# range_cape.net
KiCad netlist of a schematic drawn in EAGLE
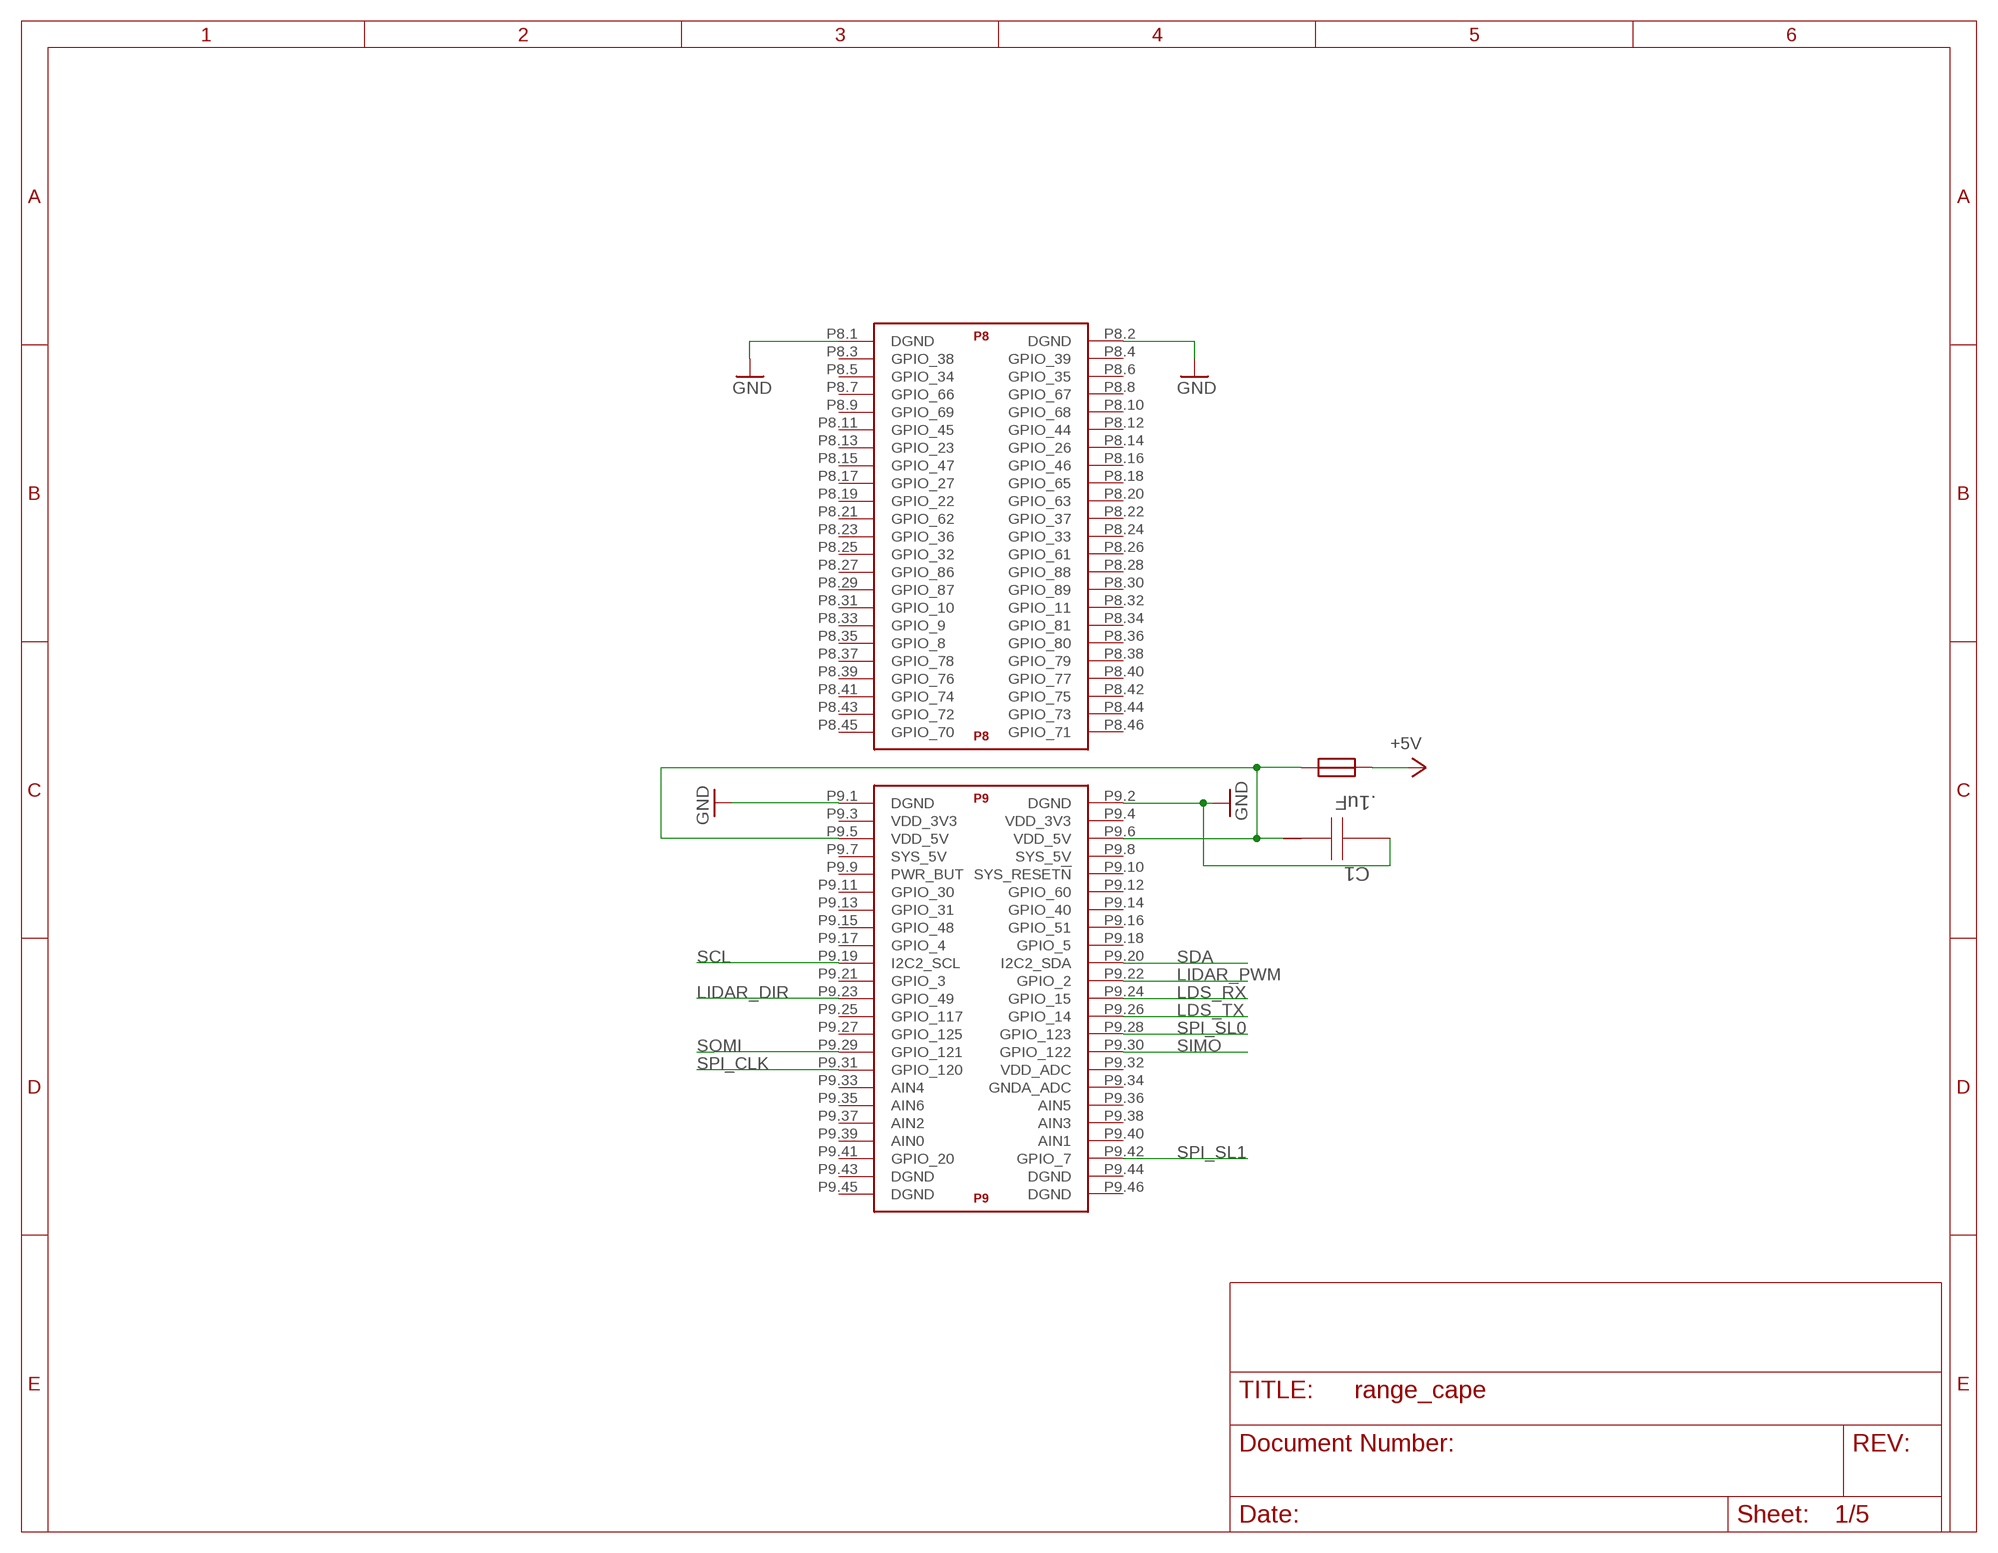
[diagram p0: schematic, sheet 1]
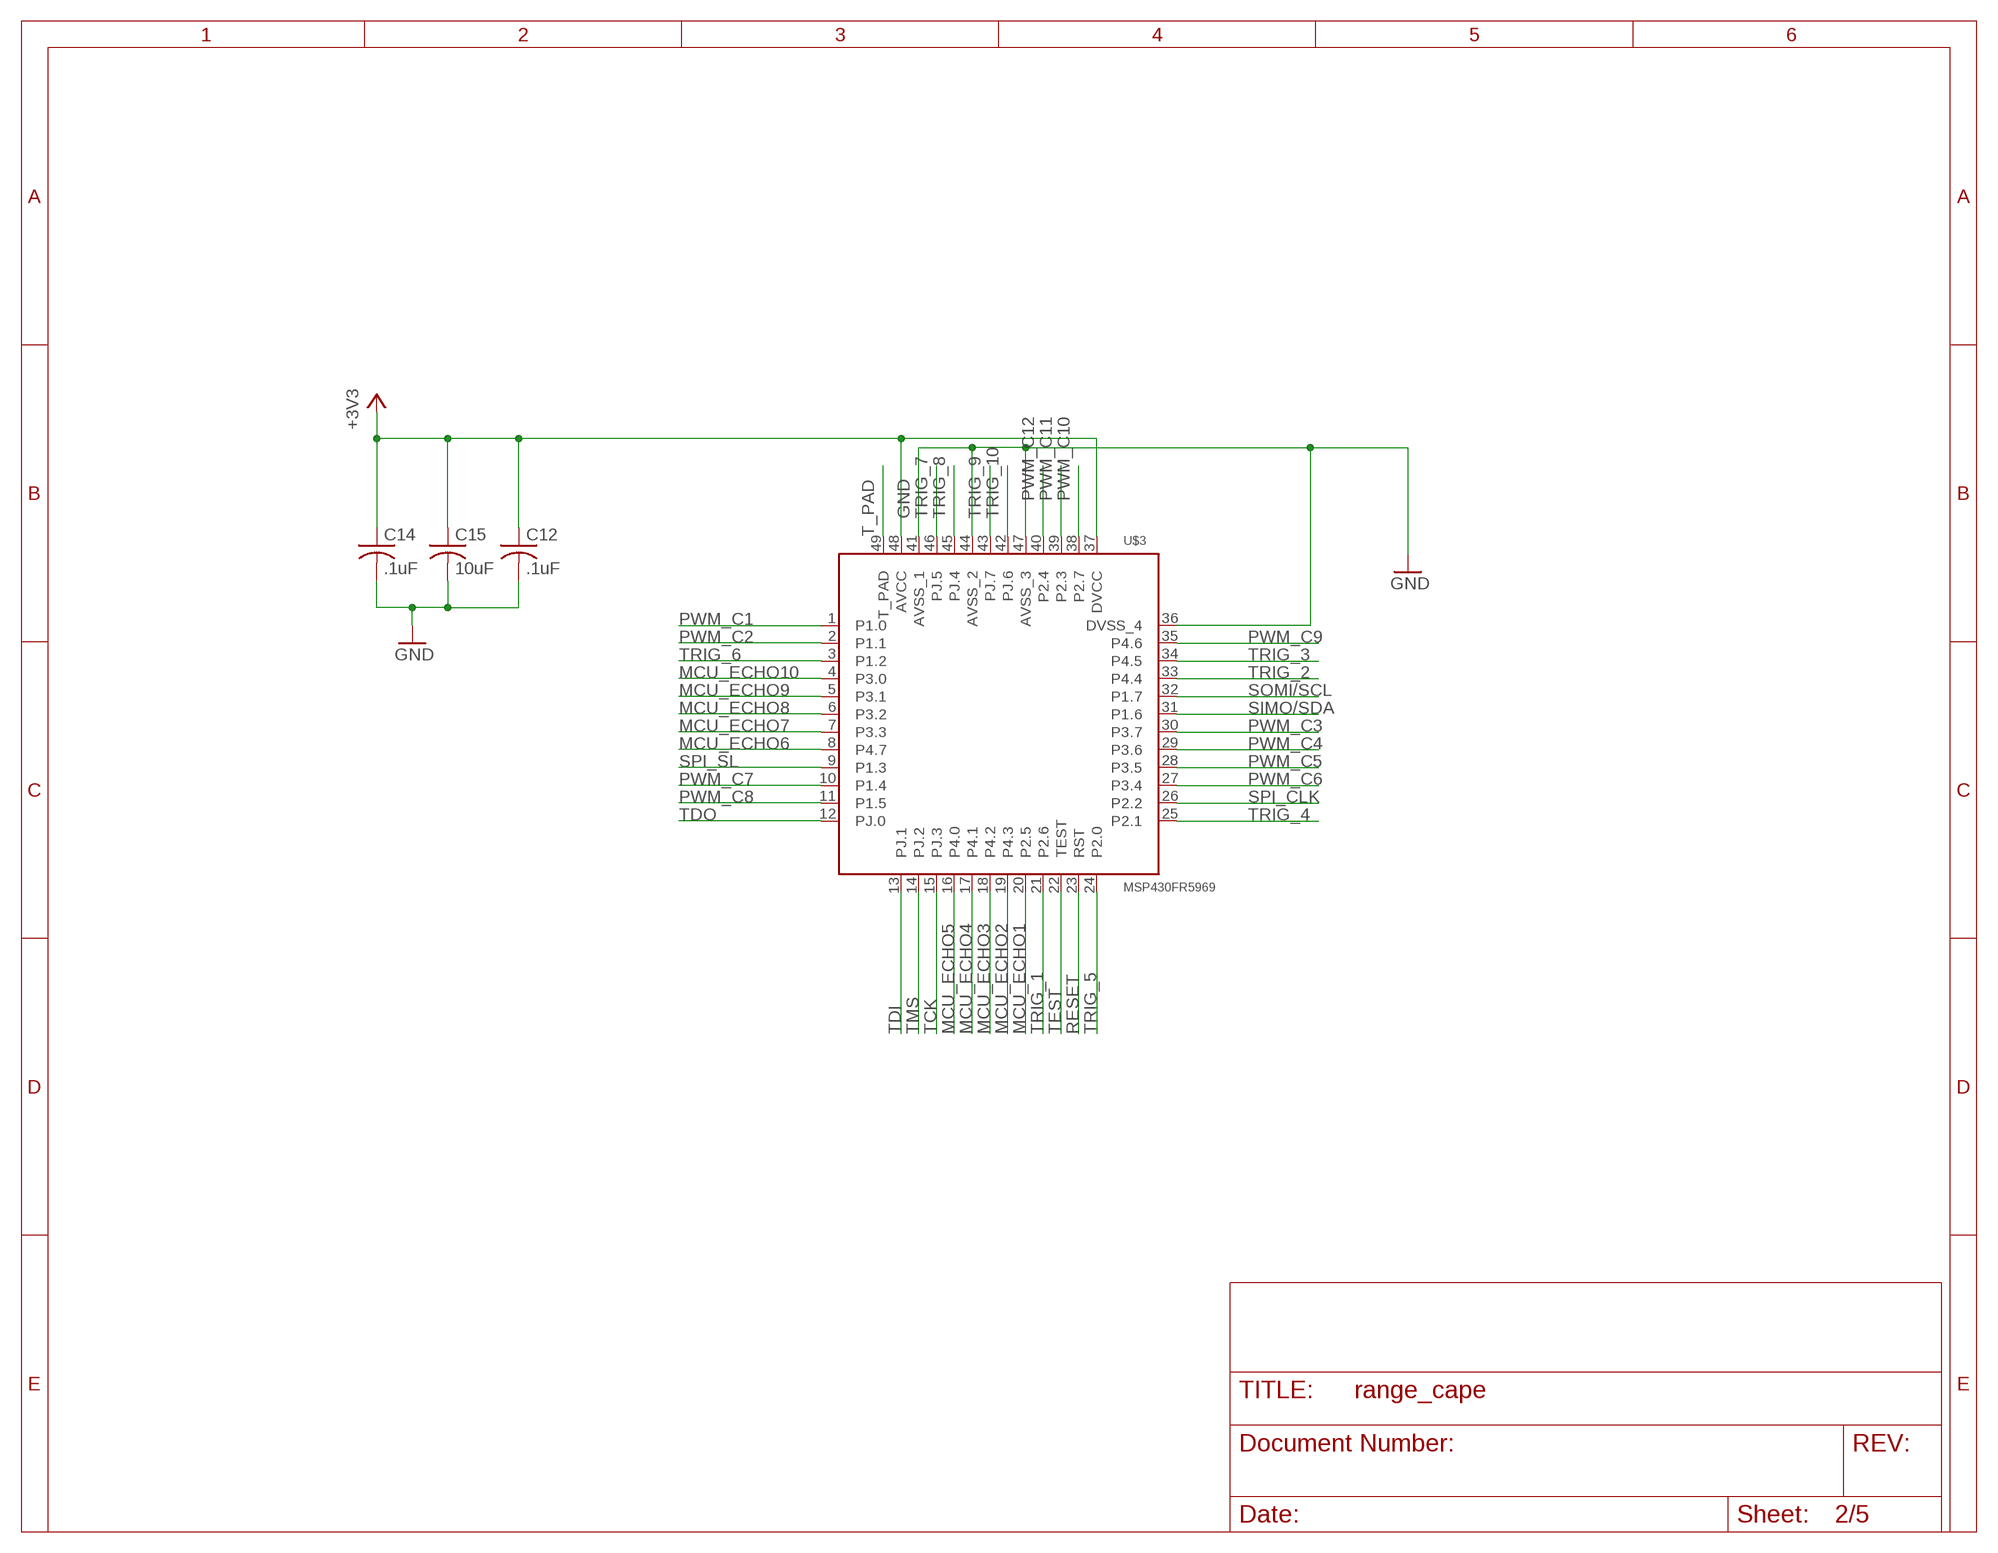
[diagram p1: schematic, sheet 2]
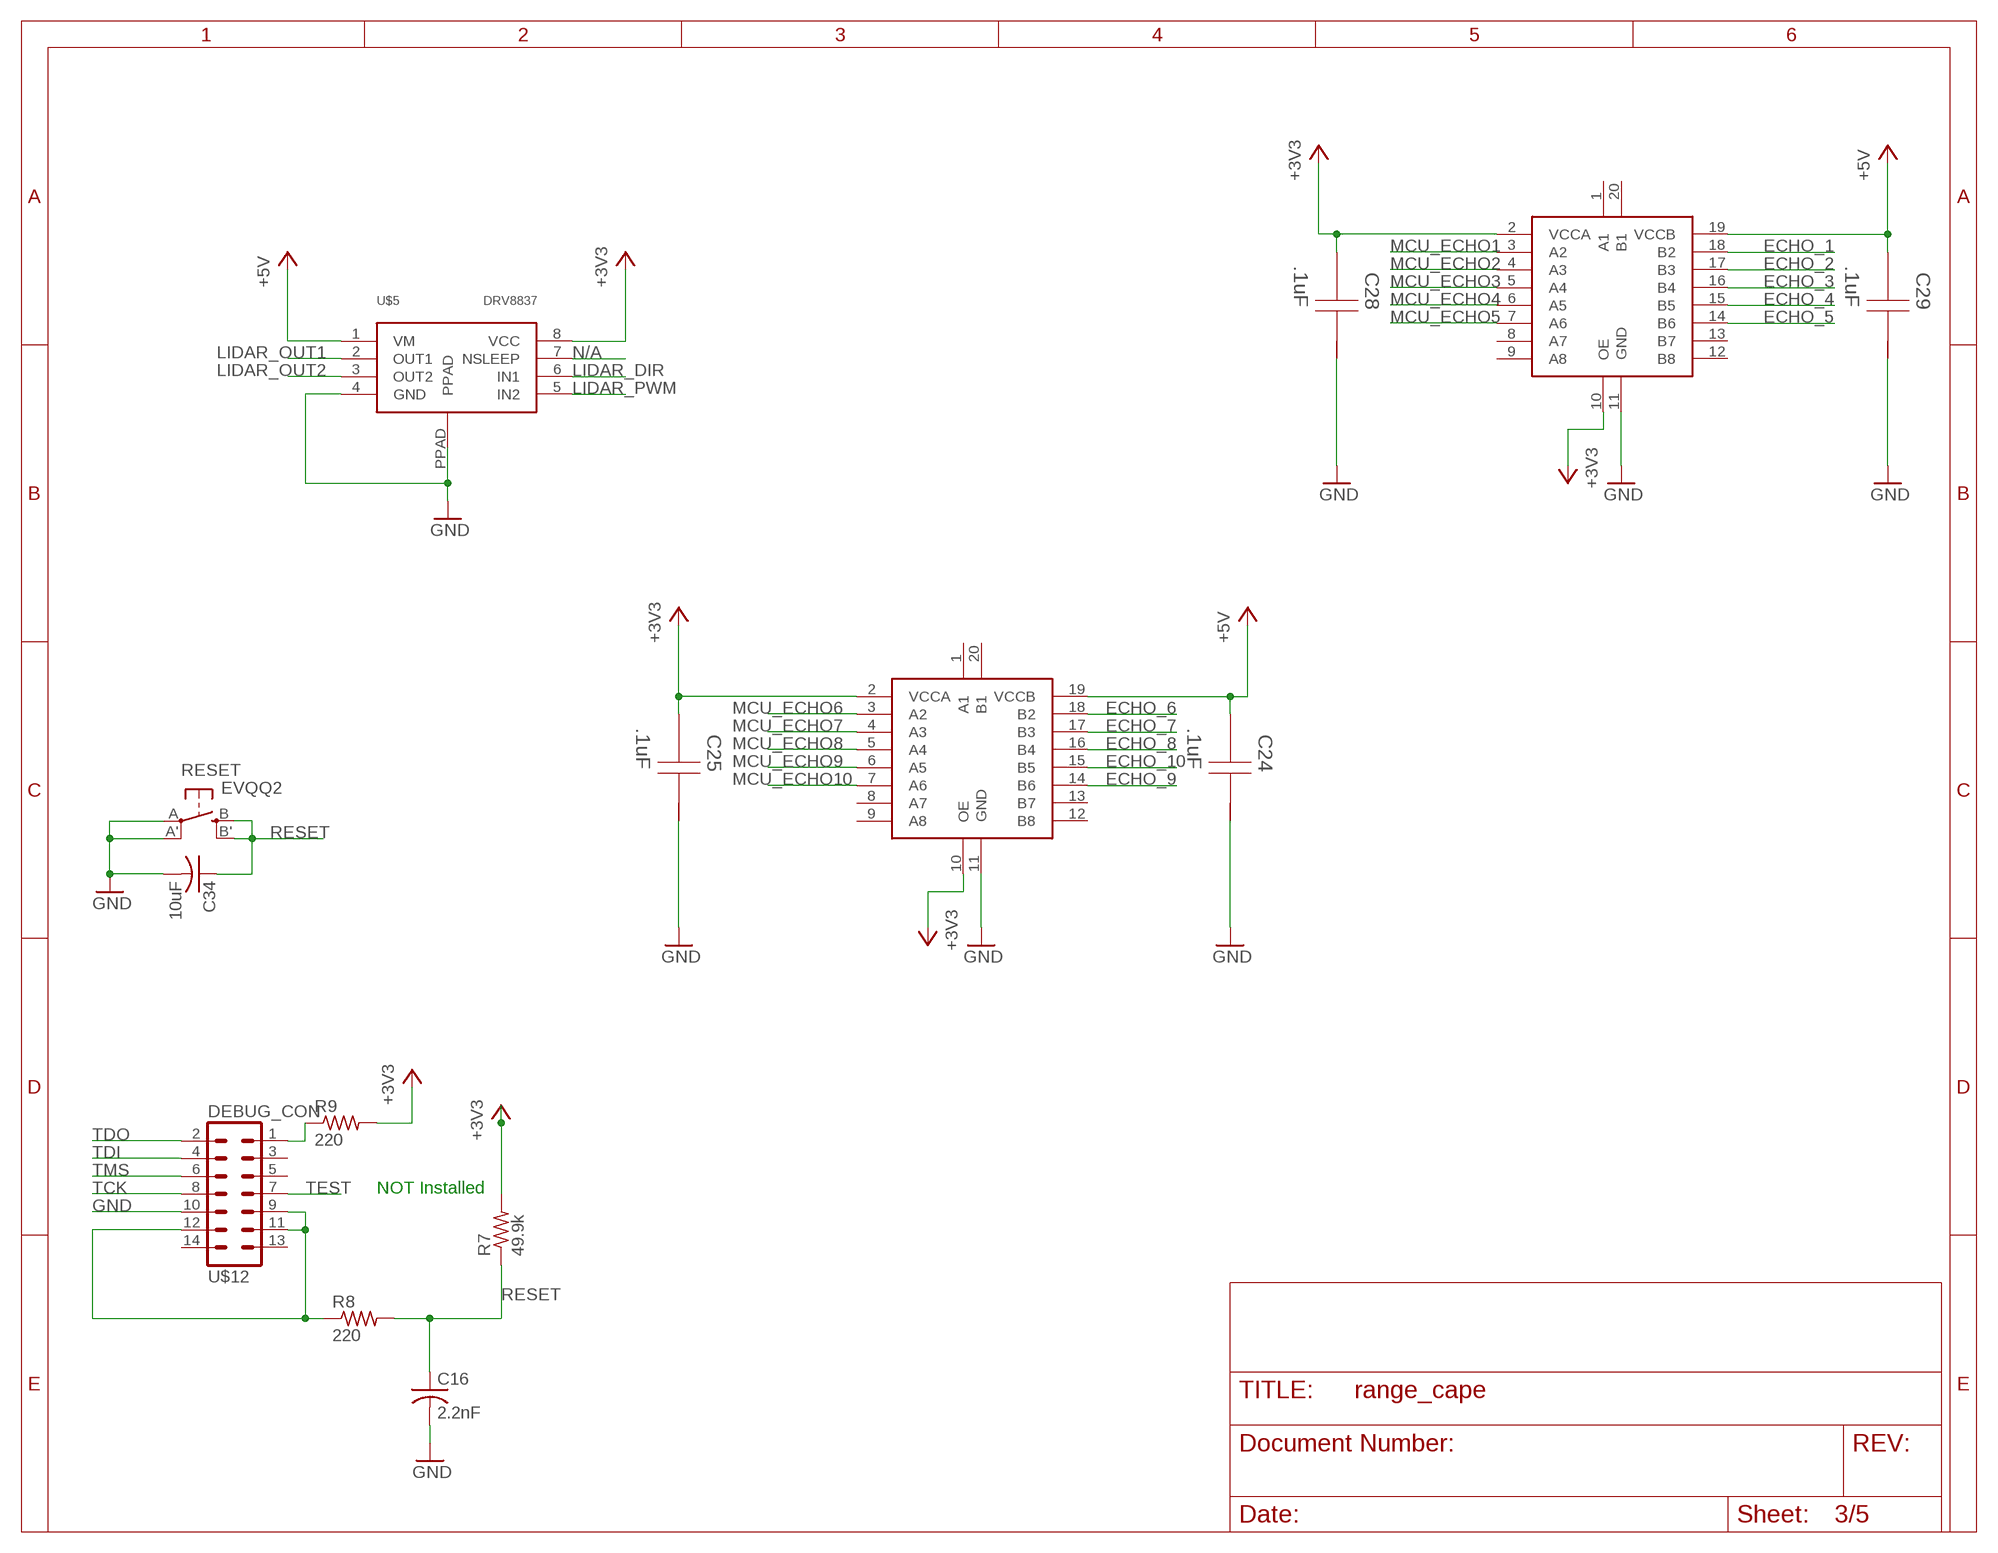
[diagram p2: schematic, sheet 3]
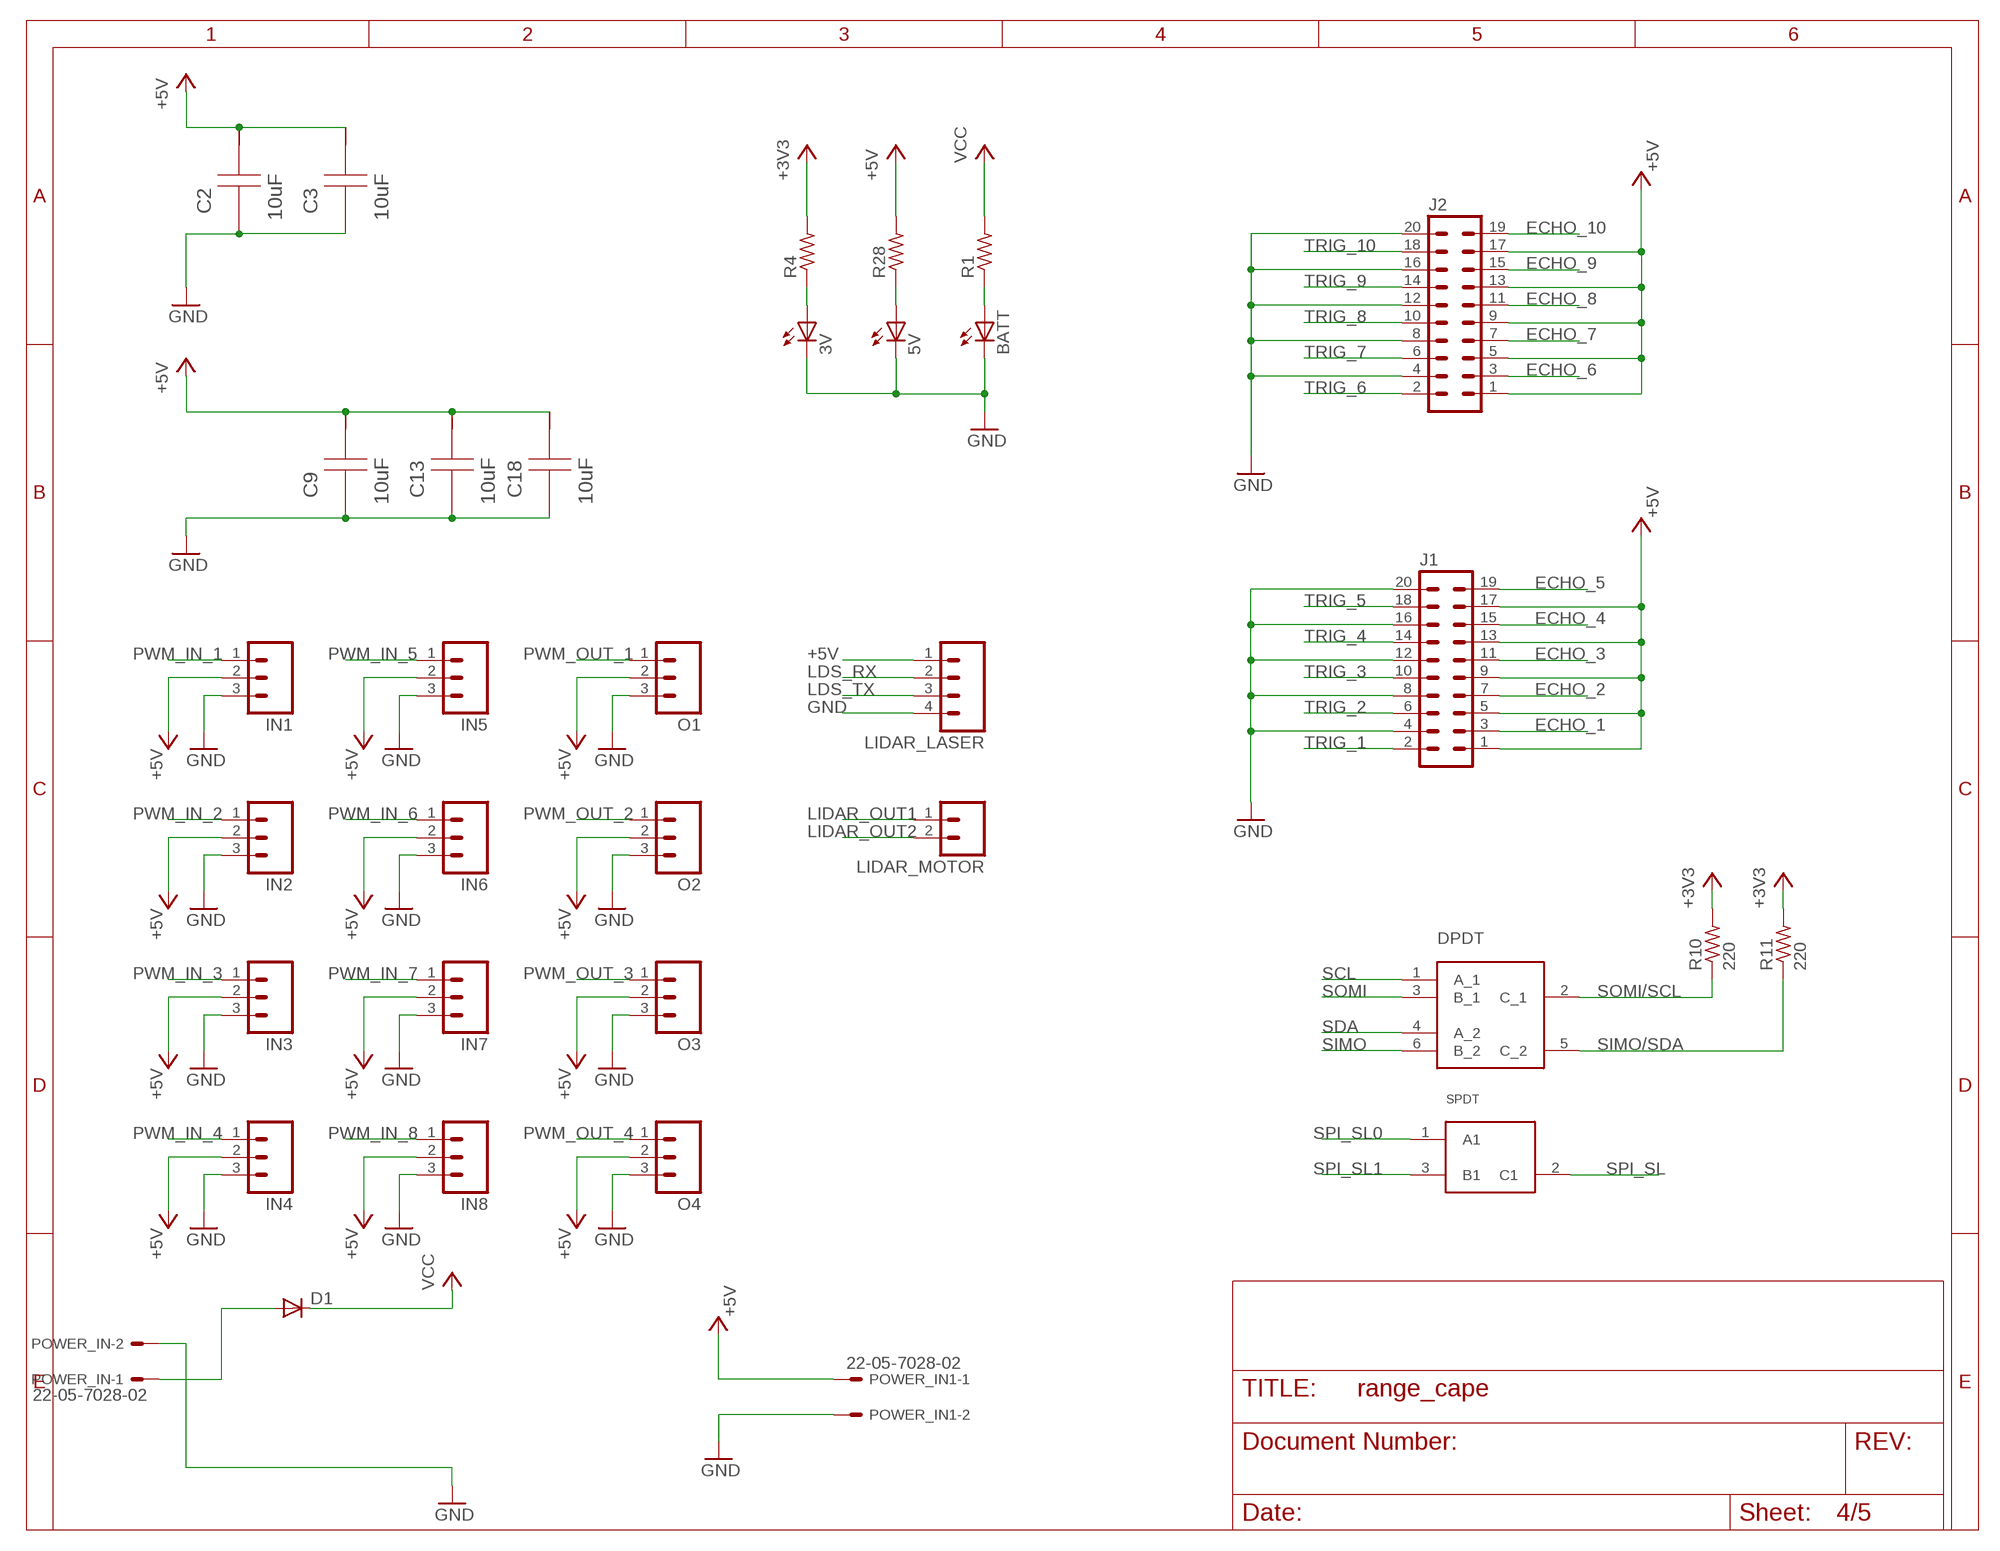
[diagram p3: schematic, sheet 4]
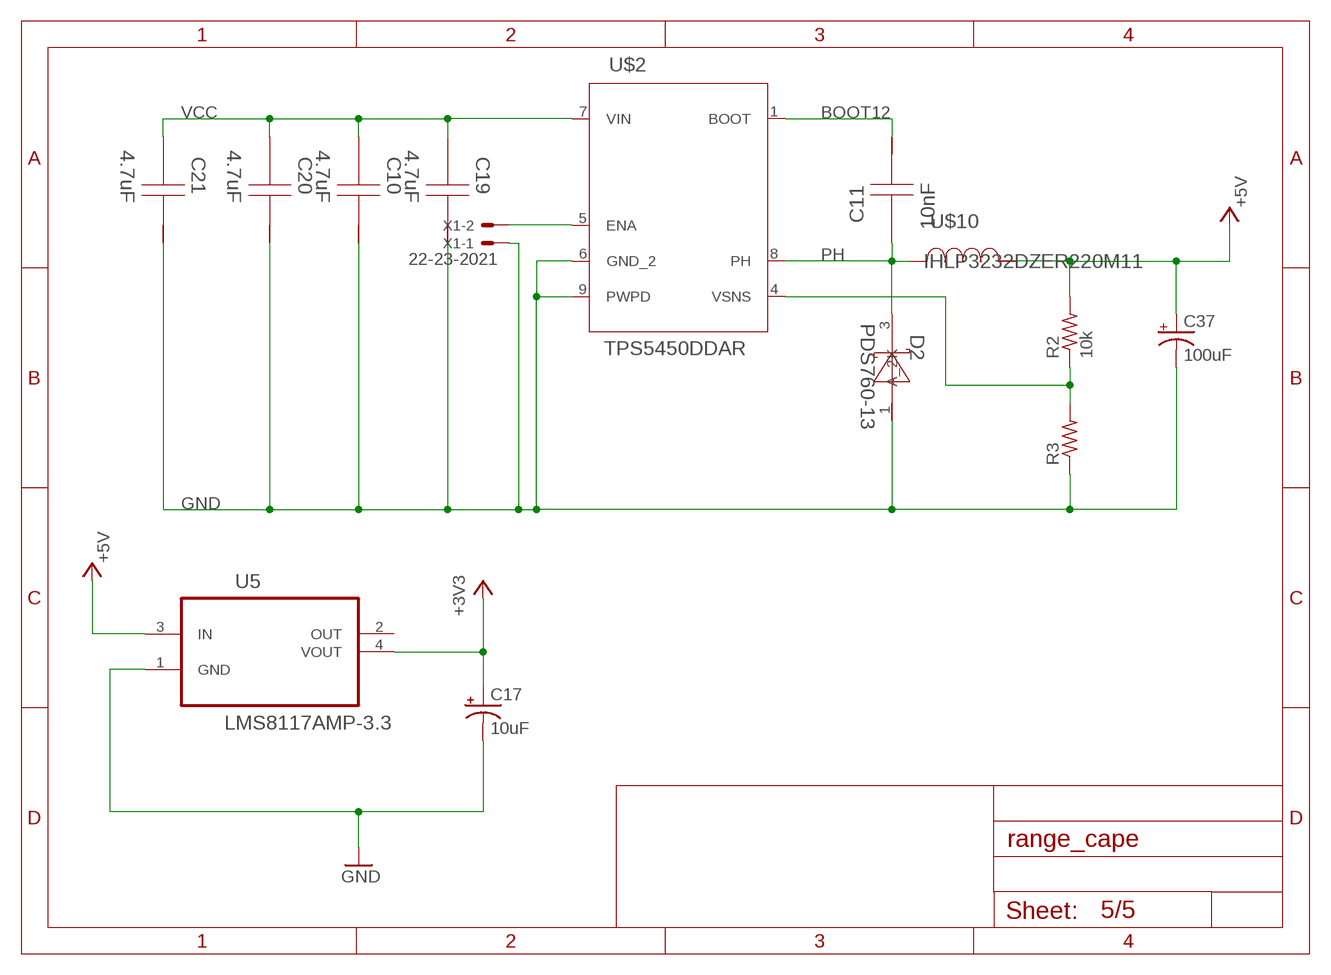
[diagram p4: schematic, sheet 5]

(export (version "E")
  (design (tool "Eeschema 10.0.6"))
  (components
    (comp (ref "C16")
      (value "2.2nF")
      (footprint "eagle-import:C0603")
      (libsource (lib "eagle-import") (part "C-USC0603"))
    )
    (comp (ref "C24")
      (value ".1uF")
      (footprint "eagle-import:1206")
      (fields (field (name "MANUFACTURER_PART_NUMBER") "C3216X5R1A106K"))
      (libsource (lib "eagle-import") (part "C3216X5R1A106K"))
    )
    (comp (ref "C25")
      (value ".1uF")
      (footprint "eagle-import:1206")
      (fields (field (name "MANUFACTURER_PART_NUMBER") "C3216X5R1A106K"))
      (libsource (lib "eagle-import") (part "C3216X5R1A106K"))
    )
    (comp (ref "C28")
      (value ".1uF")
      (footprint "eagle-import:1206")
      (fields (field (name "MANUFACTURER_PART_NUMBER") "C3216X5R1A106K"))
      (libsource (lib "eagle-import") (part "C3216X5R1A106K"))
    )
    (comp (ref "C29")
      (value ".1uF")
      (footprint "eagle-import:1206")
      (fields (field (name "MANUFACTURER_PART_NUMBER") "C3216X5R1A106K"))
      (libsource (lib "eagle-import") (part "C3216X5R1A106K"))
    )
    (comp (ref "C34")
      (value "10uF")
      (footprint "eagle-import:C1206")
      (libsource (lib "eagle-import") (part "C-USC1206"))
    )
    (comp (ref "R7")
      (value "49.9k")
      (footprint "eagle-import:R0603")
      (libsource (lib "eagle-import") (part "rcl_R-US_R0603"))
    )
    (comp (ref "R8")
      (value "220")
      (footprint "eagle-import:R0603")
      (libsource (lib "eagle-import") (part "rcl_R-US_R0603"))
    )
    (comp (ref "R9")
      (value "220")
      (footprint "eagle-import:R0603")
      (libsource (lib "eagle-import") (part "rcl_R-US_R0603"))
    )
    (comp (ref "RESET")
      (value "EVQQ2")
      (footprint "eagle-import:EVQ-Q2")
      (libsource (lib "eagle-import") (part "EVQQ2"))
    )
    (comp (ref "U$5")
      (value "DRV8837")
      (footprint "eagle-import:WSON-8")
      (libsource (lib "eagle-import") (part "DRV8837"))
    )
    (comp (ref "U$6")
      (value "TXB0108")
      (footprint "eagle-import:TSSOP-20")
      (libsource (lib "eagle-import") (part "TXB0108"))
    )
    (comp (ref "U$8")
      (value "TXB0108")
      (footprint "eagle-import:TSSOP-20")
      (libsource (lib "eagle-import") (part "TXB0108"))
    )
    (comp (ref "U$12")
      (value "DEBUG_CON")
      (footprint "eagle-import:DEBUG_SM")
      (libsource (lib "eagle-import") (part "DEBUG_CON"))
    )
    (comp (ref "C10")
      (value "4.7uF")
      (footprint "eagle-import:1206")
      (fields (field (name "MANUFACTURER_PART_NUMBER") "GRM31CR71H475KA12L"))
      (libsource (lib "eagle-import") (part "GRM31CR71H475KA12L"))
    )
    (comp (ref "C11")
      (value "10nF")
      (footprint "eagle-import:0805")
      (fields (field (name "MANUFACTURER_PART_NUMBER") "C0805C103K5RACTU"))
      (libsource (lib "eagle-import") (part "C0805C103K5RACTU"))
    )
    (comp (ref "C17")
      (value "10uF")
      (footprint "eagle-import:EIA3216")
      (libsource (lib "eagle-import") (part "10UF-16V-10%(TANT)"))
    )
    (comp (ref "C19")
      (value "4.7uF")
      (footprint "eagle-import:1206")
      (fields (field (name "MANUFACTURER_PART_NUMBER") "GRM31CR71H475KA12L"))
      (libsource (lib "eagle-import") (part "GRM31CR71H475KA12L"))
    )
    (comp (ref "C20")
      (value "4.7uF")
      (footprint "eagle-import:1206")
      (fields (field (name "MANUFACTURER_PART_NUMBER") "GRM31CR71H475KA12L"))
      (libsource (lib "eagle-import") (part "GRM31CR71H475KA12L"))
    )
    (comp (ref "C21")
      (value "4.7uF")
      (footprint "eagle-import:1206")
      (fields (field (name "MANUFACTURER_PART_NUMBER") "GRM31CR71H475KA12L"))
      (libsource (lib "eagle-import") (part "GRM31CR71H475KA12L"))
    )
    (comp (ref "C37")
      (value "100uF")
      (footprint "eagle-import:EIA7343")
      (libsource (lib "eagle-import") (part "100UF-10V-10%(TANT)"))
    )
    (comp (ref "D2")
      (value "PDS760-13")
      (footprint "eagle-import:POWERDI5")
      (libsource (lib "eagle-import") (part "PDS760-13"))
    )
    (comp (ref "R2")
      (value "10k")
      (footprint "eagle-import:M0805")
      (libsource (lib "eagle-import") (part "R-US_M0805"))
    )
    (comp (ref "R3")
      (value "R-US_M0805")
      (footprint "eagle-import:M0805")
      (libsource (lib "eagle-import") (part "R-US_M0805"))
    )
    (comp (ref "U$2")
      (value "TPS5450DDAR")
      (footprint "eagle-import:R-PDSO-G8")
      (fields (field (name "MANUFACTURER_PART_NUMBER") "TPS5450DDA"))
      (libsource (lib "eagle-import") (part "TPS5450DDAR"))
    )
    (comp (ref "U$10")
      (value "IHLP3232DZER220M11")
      (footprint "eagle-import:IHLP-3232DZ")
      (fields (field (name "MANUFACTURER") "Vishay"))
      (libsource (lib "eagle-import") (part "IHLP3232DZER220M11"))
    )
    (comp (ref "U5")
      (value "LMS8117AMP-3.3")
      (footprint "eagle-import:SOT230P696X180-4N")
      (libsource (lib "eagle-import") (part "LMS8117AMP-3.3"))
    )
    (comp (ref "X1")
      (value "22-23-2021")
      (footprint "eagle-import:22-23-2021")
      (fields (field (name "MF") "MOLEX"))
      (libsource (lib "eagle-import") (part "22-23-2021"))
    )
    (comp (ref "3V")
      (value "LED_ESML0603")
      (footprint "eagle-import:LED_SML0603")
      (libsource (lib "eagle-import") (part "LED_ESML0603"))
    )
    (comp (ref "5V")
      (value "LED_ESML0603")
      (footprint "eagle-import:LED_SML0603")
      (libsource (lib "eagle-import") (part "LED_ESML0603"))
    )
    (comp (ref "BATT")
      (value "LED_ESML0603")
      (footprint "eagle-import:LED_SML0603")
      (libsource (lib "eagle-import") (part "LED_ESML0603"))
    )
    (comp (ref "C2")
      (value "10uF")
      (footprint "eagle-import:1206")
      (fields (field (name "MANUFACTURER_PART_NUMBER") "C3216X5R1A106K"))
      (libsource (lib "eagle-import") (part "C3216X5R1A106K"))
    )
    (comp (ref "C3")
      (value "10uF")
      (footprint "eagle-import:1206")
      (fields (field (name "MANUFACTURER_PART_NUMBER") "C3216X5R1A106K"))
      (libsource (lib "eagle-import") (part "C3216X5R1A106K"))
    )
    (comp (ref "C9")
      (value "10uF")
      (footprint "eagle-import:1206")
      (fields (field (name "MANUFACTURER_PART_NUMBER") "C3216X5R1A106K"))
      (libsource (lib "eagle-import") (part "C3216X5R1A106K"))
    )
    (comp (ref "C13")
      (value "10uF")
      (footprint "eagle-import:1206")
      (fields (field (name "MANUFACTURER_PART_NUMBER") "C3216X5R1A106K"))
      (libsource (lib "eagle-import") (part "C3216X5R1A106K"))
    )
    (comp (ref "C18")
      (value "10uF")
      (footprint "eagle-import:1206")
      (fields (field (name "MANUFACTURER_PART_NUMBER") "C3216X5R1A106K"))
      (libsource (lib "eagle-import") (part "C3216X5R1A106K"))
    )
    (comp (ref "D1")
      (value "DIODE-DO-214AC")
      (footprint "eagle-import:DO-214AC")
      (libsource (lib "eagle-import") (part "DIODE-DO-214AC"))
    )
    (comp (ref "IN1")
      (value "M03LOCK")
      (footprint "eagle-import:1X03_LOCK")
      (libsource (lib "eagle-import") (part "M03LOCK"))
    )
    (comp (ref "IN2")
      (value "M03LOCK")
      (footprint "eagle-import:1X03_LOCK")
      (libsource (lib "eagle-import") (part "M03LOCK"))
    )
    (comp (ref "IN3")
      (value "M03LOCK")
      (footprint "eagle-import:1X03_LOCK")
      (libsource (lib "eagle-import") (part "M03LOCK"))
    )
    (comp (ref "IN4")
      (value "M03LOCK")
      (footprint "eagle-import:1X03_LOCK")
      (libsource (lib "eagle-import") (part "M03LOCK"))
    )
    (comp (ref "IN5")
      (value "M03LOCK")
      (footprint "eagle-import:1X03_LOCK")
      (libsource (lib "eagle-import") (part "M03LOCK"))
    )
    (comp (ref "IN6")
      (value "M03LOCK")
      (footprint "eagle-import:1X03_LOCK")
      (libsource (lib "eagle-import") (part "M03LOCK"))
    )
    (comp (ref "IN7")
      (value "M03LOCK")
      (footprint "eagle-import:1X03_LOCK")
      (libsource (lib "eagle-import") (part "M03LOCK"))
    )
    (comp (ref "IN8")
      (value "M03LOCK")
      (footprint "eagle-import:1X03_LOCK")
      (libsource (lib "eagle-import") (part "M03LOCK"))
    )
    (comp (ref "J1")
      (value "MA10-2")
      (footprint "eagle-import:MA10-2")
      (libsource (lib "eagle-import") (part "MA10-2"))
    )
    (comp (ref "J2")
      (value "MA10-2")
      (footprint "eagle-import:MA10-2")
      (libsource (lib "eagle-import") (part "MA10-2"))
    )
    (comp (ref "LIDAR_LASER")
      (value "M04JST-PTH-VERT")
      (footprint "eagle-import:JST-4-PTH-VERT")
      (libsource (lib "eagle-import") (part "M04JST-PTH-VERT"))
    )
    (comp (ref "LIDAR_MOTOR")
      (value "M02JST-PTH-VERT")
      (footprint "eagle-import:JST-2-PTH-VERT")
      (libsource (lib "eagle-import") (part "M02JST-PTH-VERT"))
    )
    (comp (ref "O1")
      (value "M03LOCK")
      (footprint "eagle-import:1X03_LOCK")
      (libsource (lib "eagle-import") (part "M03LOCK"))
    )
    (comp (ref "O2")
      (value "M03LOCK")
      (footprint "eagle-import:1X03_LOCK")
      (libsource (lib "eagle-import") (part "M03LOCK"))
    )
    (comp (ref "O3")
      (value "M03LOCK")
      (footprint "eagle-import:1X03_LOCK")
      (libsource (lib "eagle-import") (part "M03LOCK"))
    )
    (comp (ref "O4")
      (value "M03LOCK")
      (footprint "eagle-import:1X03_LOCK")
      (libsource (lib "eagle-import") (part "M03LOCK"))
    )
    (comp (ref "POWER_IN")
      (value "22-05-7028-02")
      (footprint "eagle-import:7395-02")
      (libsource (lib "eagle-import") (part "22-?-0205-7028"))
    )
    (comp (ref "POWER_IN1")
      (value "22-05-7028-02")
      (footprint "eagle-import:7395-02")
      (libsource (lib "eagle-import") (part "22-?-0205-7028"))
    )
    (comp (ref "R1")
      (value "R-US_R0603")
      (footprint "eagle-import:R0603")
      (libsource (lib "eagle-import") (part "rcl_R-US_R0603"))
    )
    (comp (ref "R4")
      (value "R-US_R0603")
      (footprint "eagle-import:R0603")
      (libsource (lib "eagle-import") (part "rcl_R-US_R0603"))
    )
    (comp (ref "R10")
      (value "220")
      (footprint "eagle-import:R0402")
      (libsource (lib "eagle-import") (part "rcl_R-US_R0402"))
    )
    (comp (ref "R11")
      (value "220")
      (footprint "eagle-import:R0402")
      (libsource (lib "eagle-import") (part "rcl_R-US_R0402"))
    )
    (comp (ref "R28")
      (value "R-US_R0603")
      (footprint "eagle-import:R0603")
      (libsource (lib "eagle-import") (part "rcl_R-US_R0603"))
    )
    (comp (ref "SPDT")
      (value "SPDT_SWITCH")
      (footprint "eagle-import:SPDT")
      (libsource (lib "eagle-import") (part "SPDT_SWITCH"))
    )
    (comp (ref "U$4")
      (value "DPDT_I2C_SPI")
      (footprint "eagle-import:DPDT")
      (libsource (lib "eagle-import") (part "DPDT_I2C_SPI"))
    )
    (comp (ref "C12")
      (value ".1uF")
      (footprint "eagle-import:C0805")
      (libsource (lib "eagle-import") (part "C-USC0805"))
    )
    (comp (ref "C14")
      (value ".1uF")
      (footprint "eagle-import:C0805")
      (libsource (lib "eagle-import") (part "C-USC0805"))
    )
    (comp (ref "C15")
      (value "10uF")
      (footprint "eagle-import:C0805")
      (libsource (lib "eagle-import") (part "C-USC0805"))
    )
    (comp (ref "U$3")
      (value "MSP430FR5969")
      (footprint "eagle-import:QFN50P700X700X100-49N")
      (libsource (lib "eagle-import") (part "MSP430FR5969"))
    )
    (comp (ref "C1")
      (value ".1uF")
      (footprint "eagle-import:1206")
      (fields (field (name "MANUFACTURER_PART_NUMBER") "C3216X5R1A106K"))
      (libsource (lib "eagle-import") (part "C3216X5R1A106K"))
    )
    (comp (ref "U$1")
      (value "BEAGLE_BONE_BLACK_CAPE")
      (footprint "eagle-import:BEAGLE_BONE_BLACK_CAPE")
      (libsource (lib "eagle-import") (part "BEAGLE_BONE_BLACK_CAPE"))
    )
    (comp (ref "U$11")
      (value "NANO_FUSE")
      (footprint "eagle-import:NANO_FUSE")
      (libsource (lib "eagle-import") (part "NANO_FUSE"))
    )
  )
  (nets
    (net (code "1") (name "+3V3") (class "Default")
      (node (ref "C12") (pin "1") (pinfunction "1_1") (pintype "passive"))
      (node (ref "C14") (pin "1") (pinfunction "1_1") (pintype "passive"))
      (node (ref "C15") (pin "1") (pinfunction "1_1") (pintype "passive"))
      (node (ref "C17") (pin "A") (pinfunction "+_A") (pintype "passive"))
      (node (ref "C25") (pin "2") (pinfunction "2_2") (pintype "passive"))
      (node (ref "C28") (pin "2") (pinfunction "2_2") (pintype "passive"))
      (node (ref "R10") (pin "2") (pinfunction "2_2") (pintype "passive"))
      (node (ref "R11") (pin "2") (pinfunction "2_2") (pintype "passive"))
      (node (ref "R4") (pin "2") (pinfunction "2_2") (pintype "passive"))
      (node (ref "R7") (pin "2") (pinfunction "2_2") (pintype "passive"))
      (node (ref "R9") (pin "2") (pinfunction "2_2") (pintype "passive"))
      (node (ref "U$3") (pin "37") (pinfunction "DVCC_37") (pintype "power_in"))
      (node (ref "U$3") (pin "48") (pinfunction "AVCC_48") (pintype "power_in"))
      (node (ref "U$5") (pin "8") (pinfunction "VCC_8") (pintype "bidirectional"))
      (node (ref "U$6") (pin "10") (pinfunction "OE_10") (pintype "bidirectional"))
      (node (ref "U$6") (pin "2") (pinfunction "VCCA_2") (pintype "bidirectional"))
      (node (ref "U$8") (pin "10") (pinfunction "OE_10") (pintype "bidirectional"))
      (node (ref "U$8") (pin "2") (pinfunction "VCCA_2") (pintype "bidirectional"))
      (node (ref "U5") (pin "4") (pinfunction "VOUT_4") (pintype "power_in"))
    )
    (net (code "2") (name "+5V") (class "Default")
      (node (ref "C13") (pin "1") (pinfunction "1_1") (pintype "passive"))
      (node (ref "C18") (pin "1") (pinfunction "1_1") (pintype "passive"))
      (node (ref "C2") (pin "1") (pinfunction "1_1") (pintype "passive"))
      (node (ref "C24") (pin "2") (pinfunction "2_2") (pintype "passive"))
      (node (ref "C29") (pin "2") (pinfunction "2_2") (pintype "passive"))
      (node (ref "C3") (pin "1") (pinfunction "1_1") (pintype "passive"))
      (node (ref "C37") (pin "A") (pinfunction "+_A") (pintype "passive"))
      (node (ref "C9") (pin "1") (pinfunction "1_1") (pintype "passive"))
      (node (ref "IN1") (pin "2") (pinfunction "2_2") (pintype "passive"))
      (node (ref "IN2") (pin "2") (pinfunction "2_2") (pintype "passive"))
      (node (ref "IN3") (pin "2") (pinfunction "2_2") (pintype "passive"))
      (node (ref "IN4") (pin "2") (pinfunction "2_2") (pintype "passive"))
      (node (ref "IN5") (pin "2") (pinfunction "2_2") (pintype "passive"))
      (node (ref "IN6") (pin "2") (pinfunction "2_2") (pintype "passive"))
      (node (ref "IN7") (pin "2") (pinfunction "2_2") (pintype "passive"))
      (node (ref "IN8") (pin "2") (pinfunction "2_2") (pintype "passive"))
      (node (ref "J1") (pin "1") (pinfunction "1_1") (pintype "passive"))
      (node (ref "J1") (pin "13") (pinfunction "13_13") (pintype "passive"))
      (node (ref "J1") (pin "17") (pinfunction "17_17") (pintype "passive"))
      (node (ref "J1") (pin "5") (pinfunction "5_5") (pintype "passive"))
      (node (ref "J1") (pin "9") (pinfunction "9_9") (pintype "passive"))
      (node (ref "J2") (pin "1") (pinfunction "1_1") (pintype "passive"))
      (node (ref "J2") (pin "13") (pinfunction "13_13") (pintype "passive"))
      (node (ref "J2") (pin "17") (pinfunction "17_17") (pintype "passive"))
      (node (ref "J2") (pin "5") (pinfunction "5_5") (pintype "passive"))
      (node (ref "J2") (pin "9") (pinfunction "9_9") (pintype "passive"))
      (node (ref "LIDAR_LASER") (pin "1") (pinfunction "1_1") (pintype "passive"))
      (node (ref "O1") (pin "2") (pinfunction "2_2") (pintype "passive"))
      (node (ref "O2") (pin "2") (pinfunction "2_2") (pintype "passive"))
      (node (ref "O3") (pin "2") (pinfunction "2_2") (pintype "passive"))
      (node (ref "O4") (pin "2") (pinfunction "2_2") (pintype "passive"))
      (node (ref "POWER_IN1") (pin "1") (pinfunction "S_1") (pintype "passive"))
      (node (ref "R2") (pin "2") (pinfunction "2_2") (pintype "passive"))
      (node (ref "R28") (pin "2") (pinfunction "2_2") (pintype "passive"))
      (node (ref "U$10") (pin "2") (pinfunction "2_2") (pintype "passive"))
      (node (ref "U$11") (pin "2") (pinfunction "2_2") (pintype "bidirectional"))
      (node (ref "U$5") (pin "1") (pinfunction "VM_1") (pintype "bidirectional"))
      (node (ref "U$6") (pin "19") (pinfunction "VCCB_19") (pintype "bidirectional"))
      (node (ref "U$8") (pin "19") (pinfunction "VCCB_19") (pintype "bidirectional"))
      (node (ref "U5") (pin "3") (pinfunction "IN_3") (pintype "power_in"))
    )
    (net (code "3") (name "BOOT12") (class "Default")
      (node (ref "C11") (pin "1") (pinfunction "1_1") (pintype "passive"))
      (node (ref "U$2") (pin "1") (pinfunction "BOOT_1") (pintype "passive"))
    )
    (net (code "4") (name "ECHO_1") (class "Default")
      (node (ref "J1") (pin "3") (pinfunction "3_3") (pintype "passive"))
      (node (ref "U$6") (pin "18") (pinfunction "B2_18") (pintype "bidirectional"))
    )
    (net (code "5") (name "ECHO_2") (class "Default")
      (node (ref "J1") (pin "7") (pinfunction "7_7") (pintype "passive"))
      (node (ref "U$6") (pin "17") (pinfunction "B3_17") (pintype "bidirectional"))
    )
    (net (code "6") (name "ECHO_3") (class "Default")
      (node (ref "J1") (pin "11") (pinfunction "11_11") (pintype "passive"))
      (node (ref "U$6") (pin "16") (pinfunction "B4_16") (pintype "bidirectional"))
    )
    (net (code "7") (name "ECHO_4") (class "Default")
      (node (ref "J1") (pin "15") (pinfunction "15_15") (pintype "passive"))
      (node (ref "U$6") (pin "15") (pinfunction "B5_15") (pintype "bidirectional"))
    )
    (net (code "8") (name "ECHO_5") (class "Default")
      (node (ref "J1") (pin "19") (pinfunction "19_19") (pintype "passive"))
      (node (ref "U$6") (pin "14") (pinfunction "B6_14") (pintype "bidirectional"))
    )
    (net (code "9") (name "ECHO_6") (class "Default")
      (node (ref "J2") (pin "3") (pinfunction "3_3") (pintype "passive"))
      (node (ref "U$8") (pin "18") (pinfunction "B2_18") (pintype "bidirectional"))
    )
    (net (code "10") (name "ECHO_7") (class "Default")
      (node (ref "J2") (pin "7") (pinfunction "7_7") (pintype "passive"))
      (node (ref "U$8") (pin "17") (pinfunction "B3_17") (pintype "bidirectional"))
    )
    (net (code "11") (name "ECHO_8") (class "Default")
      (node (ref "J2") (pin "11") (pinfunction "11_11") (pintype "passive"))
      (node (ref "U$8") (pin "16") (pinfunction "B4_16") (pintype "bidirectional"))
    )
    (net (code "12") (name "ECHO_9") (class "Default")
      (node (ref "J2") (pin "15") (pinfunction "15_15") (pintype "passive"))
      (node (ref "U$8") (pin "14") (pinfunction "B6_14") (pintype "bidirectional"))
    )
    (net (code "13") (name "ECHO_10") (class "Default")
      (node (ref "J2") (pin "19") (pinfunction "19_19") (pintype "passive"))
      (node (ref "U$8") (pin "15") (pinfunction "B5_15") (pintype "bidirectional"))
    )
    (net (code "14") (name "GND") (class "Default")
      (node (ref "3V") (pin "C") (pinfunction "C_C") (pintype "passive"))
      (node (ref "5V") (pin "C") (pinfunction "C_C") (pintype "passive"))
      (node (ref "BATT") (pin "C") (pinfunction "C_C") (pintype "passive"))
      (node (ref "C1") (pin "2") (pinfunction "2_2") (pintype "passive"))
      (node (ref "C10") (pin "1") (pinfunction "1_1") (pintype "passive"))
      (node (ref "C12") (pin "2") (pinfunction "2_2") (pintype "passive"))
      (node (ref "C13") (pin "2") (pinfunction "2_2") (pintype "passive"))
      (node (ref "C14") (pin "2") (pinfunction "2_2") (pintype "passive"))
      (node (ref "C15") (pin "2") (pinfunction "2_2") (pintype "passive"))
      (node (ref "C16") (pin "2") (pinfunction "2_2") (pintype "passive"))
      (node (ref "C17") (pin "C") (pinfunction "-_C") (pintype "passive"))
      (node (ref "C18") (pin "2") (pinfunction "2_2") (pintype "passive"))
      (node (ref "C19") (pin "1") (pinfunction "1_1") (pintype "passive"))
      (node (ref "C2") (pin "2") (pinfunction "2_2") (pintype "passive"))
      (node (ref "C20") (pin "1") (pinfunction "1_1") (pintype "passive"))
      (node (ref "C21") (pin "1") (pinfunction "1_1") (pintype "passive"))
      (node (ref "C24") (pin "1") (pinfunction "1_1") (pintype "passive"))
      (node (ref "C25") (pin "1") (pinfunction "1_1") (pintype "passive"))
      (node (ref "C28") (pin "1") (pinfunction "1_1") (pintype "passive"))
      (node (ref "C29") (pin "1") (pinfunction "1_1") (pintype "passive"))
      (node (ref "C3") (pin "2") (pinfunction "2_2") (pintype "passive"))
      (node (ref "C34") (pin "2") (pinfunction "2_2") (pintype "passive"))
      (node (ref "C37") (pin "C") (pinfunction "-_C") (pintype "passive"))
      (node (ref "C9") (pin "2") (pinfunction "2_2") (pintype "passive"))
      (node (ref "D2") (pin "1") (pinfunction "A_2_1") (pintype "passive"))
      (node (ref "IN1") (pin "3") (pinfunction "3_3") (pintype "passive"))
      (node (ref "IN2") (pin "3") (pinfunction "3_3") (pintype "passive"))
      (node (ref "IN3") (pin "3") (pinfunction "3_3") (pintype "passive"))
      (node (ref "IN4") (pin "3") (pinfunction "3_3") (pintype "passive"))
      (node (ref "IN5") (pin "3") (pinfunction "3_3") (pintype "passive"))
      (node (ref "IN6") (pin "3") (pinfunction "3_3") (pintype "passive"))
      (node (ref "IN7") (pin "3") (pinfunction "3_3") (pintype "passive"))
      (node (ref "IN8") (pin "3") (pinfunction "3_3") (pintype "passive"))
      (node (ref "J1") (pin "12") (pinfunction "12_12") (pintype "passive"))
      (node (ref "J1") (pin "16") (pinfunction "16_16") (pintype "passive"))
      (node (ref "J1") (pin "20") (pinfunction "20_20") (pintype "passive"))
      (node (ref "J1") (pin "4") (pinfunction "4_4") (pintype "passive"))
      (node (ref "J1") (pin "8") (pinfunction "8_8") (pintype "passive"))
      (node (ref "J2") (pin "12") (pinfunction "12_12") (pintype "passive"))
      (node (ref "J2") (pin "16") (pinfunction "16_16") (pintype "passive"))
      (node (ref "J2") (pin "20") (pinfunction "20_20") (pintype "passive"))
      (node (ref "J2") (pin "4") (pinfunction "4_4") (pintype "passive"))
      (node (ref "J2") (pin "8") (pinfunction "8_8") (pintype "passive"))
      (node (ref "LIDAR_LASER") (pin "4") (pinfunction "4_4") (pintype "passive"))
      (node (ref "O1") (pin "3") (pinfunction "3_3") (pintype "passive"))
      (node (ref "O2") (pin "3") (pinfunction "3_3") (pintype "passive"))
      (node (ref "O3") (pin "3") (pinfunction "3_3") (pintype "passive"))
      (node (ref "O4") (pin "3") (pinfunction "3_3") (pintype "passive"))
      (node (ref "POWER_IN") (pin "2") (pinfunction "S_2") (pintype "passive"))
      (node (ref "POWER_IN1") (pin "2") (pinfunction "S_2") (pintype "passive"))
      (node (ref "R3") (pin "1") (pinfunction "1_1") (pintype "passive"))
      (node (ref "RESET") (pin "A") (pinfunction "P_A") (pintype "passive"))
      (node (ref "RESET") (pin "A'") (pinfunction "P1_A'") (pintype "passive"))
      (node (ref "U$1") (pin "P8.1") (pinfunction "DGND_P8.1") (pintype "bidirectional"))
      (node (ref "U$1") (pin "P8.2") (pinfunction "DGND_P8.2") (pintype "bidirectional"))
      (node (ref "U$1") (pin "P9.1") (pinfunction "DGND_P9.1") (pintype "bidirectional"))
      (node (ref "U$1") (pin "P9.2") (pinfunction "DGND_P9.2") (pintype "bidirectional"))
      (node (ref "U$12") (pin "10") (pinfunction "10_10") (pintype "passive"))
      (node (ref "U$2") (pin "6") (pinfunction "GND_2_6") (pintype "passive"))
      (node (ref "U$2") (pin "9") (pinfunction "PWPD_9") (pintype "passive"))
      (node (ref "U$3") (pin "36") (pinfunction "DVSS_4_36") (pintype "power_in"))
      (node (ref "U$3") (pin "41") (pinfunction "AVSS_1_41") (pintype "power_in"))
      (node (ref "U$3") (pin "44") (pinfunction "AVSS_2_44") (pintype "power_in"))
      (node (ref "U$3") (pin "47") (pinfunction "AVSS_3_47") (pintype "power_in"))
      (node (ref "U$5") (pin "4") (pinfunction "GND_4") (pintype "bidirectional"))
      (node (ref "U$5") (pin "PPAD") (pinfunction "PPAD_PPAD") (pintype "bidirectional"))
      (node (ref "U$6") (pin "11") (pinfunction "GND_11") (pintype "bidirectional"))
      (node (ref "U$8") (pin "11") (pinfunction "GND_11") (pintype "bidirectional"))
      (node (ref "U5") (pin "1") (pinfunction "GND_1") (pintype "passive"))
      (node (ref "X1") (pin "1") (pinfunction "S_1") (pintype "passive"))
    )
    (net (code "15") (name "LDS_RX") (class "Default")
      (node (ref "LIDAR_LASER") (pin "2") (pinfunction "2_2") (pintype "passive"))
      (node (ref "U$1") (pin "P9.24") (pinfunction "GPIO_15_P9.24") (pintype "bidirectional"))
    )
    (net (code "16") (name "LDS_TX") (class "Default")
      (node (ref "LIDAR_LASER") (pin "3") (pinfunction "3_3") (pintype "passive"))
      (node (ref "U$1") (pin "P9.26") (pinfunction "GPIO_14_P9.26") (pintype "bidirectional"))
    )
    (net (code "17") (name "LIDAR_DIR") (class "Default")
      (node (ref "U$1") (pin "P9.23") (pinfunction "GPIO_49_P9.23") (pintype "bidirectional"))
      (node (ref "U$5") (pin "6") (pinfunction "IN1_6") (pintype "bidirectional"))
    )
    (net (code "18") (name "LIDAR_OUT1") (class "Default")
      (node (ref "LIDAR_MOTOR") (pin "1") (pinfunction "1_1") (pintype "passive"))
      (node (ref "U$5") (pin "2") (pinfunction "OUT1_2") (pintype "bidirectional"))
    )
    (net (code "19") (name "LIDAR_OUT2") (class "Default")
      (node (ref "LIDAR_MOTOR") (pin "2") (pinfunction "2_2") (pintype "passive"))
      (node (ref "U$5") (pin "3") (pinfunction "OUT2_3") (pintype "bidirectional"))
    )
    (net (code "20") (name "LIDAR_PWM") (class "Default")
      (node (ref "U$1") (pin "P9.22") (pinfunction "GPIO_2_P9.22") (pintype "bidirectional"))
      (node (ref "U$5") (pin "5") (pinfunction "IN2_5") (pintype "bidirectional"))
    )
    (net (code "21") (name "MCU_ECHO1") (class "Default")
      (node (ref "U$3") (pin "20") (pinfunction "P2.5_20") (pintype "power_in"))
      (node (ref "U$6") (pin "3") (pinfunction "A2_3") (pintype "bidirectional"))
    )
    (net (code "22") (name "MCU_ECHO2") (class "Default")
      (node (ref "U$3") (pin "19") (pinfunction "P4.3_19") (pintype "power_in"))
      (node (ref "U$6") (pin "4") (pinfunction "A3_4") (pintype "bidirectional"))
    )
    (net (code "23") (name "MCU_ECHO3") (class "Default")
      (node (ref "U$3") (pin "18") (pinfunction "P4.2_18") (pintype "power_in"))
      (node (ref "U$6") (pin "5") (pinfunction "A4_5") (pintype "bidirectional"))
    )
    (net (code "24") (name "MCU_ECHO4") (class "Default")
      (node (ref "U$3") (pin "17") (pinfunction "P4.1_17") (pintype "power_in"))
      (node (ref "U$6") (pin "6") (pinfunction "A5_6") (pintype "bidirectional"))
    )
    (net (code "25") (name "MCU_ECHO5") (class "Default")
      (node (ref "U$3") (pin "16") (pinfunction "P4.0_16") (pintype "power_in"))
      (node (ref "U$6") (pin "7") (pinfunction "A6_7") (pintype "bidirectional"))
    )
    (net (code "26") (name "MCU_ECHO6") (class "Default")
      (node (ref "U$3") (pin "8") (pinfunction "P4.7_8") (pintype "power_in"))
      (node (ref "U$8") (pin "3") (pinfunction "A2_3") (pintype "bidirectional"))
    )
    (net (code "27") (name "MCU_ECHO7") (class "Default")
      (node (ref "U$3") (pin "7") (pinfunction "P3.3_7") (pintype "power_in"))
      (node (ref "U$8") (pin "4") (pinfunction "A3_4") (pintype "bidirectional"))
    )
    (net (code "28") (name "MCU_ECHO8") (class "Default")
      (node (ref "U$3") (pin "6") (pinfunction "P3.2_6") (pintype "power_in"))
      (node (ref "U$8") (pin "5") (pinfunction "A4_5") (pintype "bidirectional"))
    )
    (net (code "29") (name "MCU_ECHO9") (class "Default")
      (node (ref "U$3") (pin "5") (pinfunction "P3.1_5") (pintype "power_in"))
      (node (ref "U$8") (pin "6") (pinfunction "A5_6") (pintype "bidirectional"))
    )
    (net (code "30") (name "MCU_ECHO10") (class "Default")
      (node (ref "U$3") (pin "4") (pinfunction "P3.0_4") (pintype "power_in"))
      (node (ref "U$8") (pin "7") (pinfunction "A6_7") (pintype "bidirectional"))
    )
    (net (code "31") (name "Net-(3V-PadA)") (class "Default")
      (node (ref "3V") (pin "A") (pinfunction "A_A") (pintype "passive"))
      (node (ref "R4") (pin "1") (pinfunction "1_1") (pintype "passive"))
    )
    (net (code "32") (name "Net-(5V-PadA)") (class "Default")
      (node (ref "5V") (pin "A") (pinfunction "A_A") (pintype "passive"))
      (node (ref "R28") (pin "1") (pinfunction "1_1") (pintype "passive"))
    )
    (net (code "33") (name "Net-(BATT-PadA)") (class "Default")
      (node (ref "BATT") (pin "A") (pinfunction "A_A") (pintype "passive"))
      (node (ref "R1") (pin "1") (pinfunction "1_1") (pintype "passive"))
    )
    (net (code "34") (name "Net-(C1-Pad1)") (class "Default")
      (node (ref "C1") (pin "1") (pinfunction "1_1") (pintype "passive"))
      (node (ref "U$1") (pin "P9.5") (pinfunction "VDD_5V_P9.5") (pintype "bidirectional"))
      (node (ref "U$1") (pin "P9.6") (pinfunction "VDD_5V_P9.6") (pintype "bidirectional"))
      (node (ref "U$11") (pin "1") (pinfunction "1_1") (pintype "bidirectional"))
    )
    (net (code "35") (name "Net-(POWER_INA-S)") (class "Default")
      (node (ref "D1") (pin "A") (pinfunction "A_A") (pintype "passive"))
      (node (ref "POWER_IN") (pin "1") (pinfunction "S_1") (pintype "passive"))
    )
    (net (code "36") (name "Net-(R8-Pad1)") (class "Default")
      (node (ref "R8") (pin "1") (pinfunction "1_1") (pintype "passive"))
      (node (ref "U$12") (pin "11") (pinfunction "11_11") (pintype "passive"))
      (node (ref "U$12") (pin "12") (pinfunction "12_12") (pintype "passive"))
      (node (ref "U$12") (pin "9") (pinfunction "9_9") (pintype "passive"))
    )
    (net (code "37") (name "Net-(R9-Pad1)") (class "Default")
      (node (ref "R9") (pin "1") (pinfunction "1_1") (pintype "passive"))
      (node (ref "U$12") (pin "1") (pinfunction "1_1") (pintype "passive"))
    )
    (net (code "38") (name "Net-(U$2-ENA)") (class "Default")
      (node (ref "U$2") (pin "5") (pinfunction "ENA_5") (pintype "passive"))
      (node (ref "X1") (pin "2") (pinfunction "S_2") (pintype "passive"))
    )
    (net (code "39") (name "Net-(U$2-VSNS)") (class "Default")
      (node (ref "R2") (pin "1") (pinfunction "1_1") (pintype "passive"))
      (node (ref "R3") (pin "2") (pinfunction "2_2") (pintype "passive"))
      (node (ref "U$2") (pin "4") (pinfunction "VSNS_4") (pintype "passive"))
    )
    (net (code "40") (name "N{slash}A") (class "Default")
      (node (ref "U$5") (pin "7") (pinfunction "NSLEEP_7") (pintype "bidirectional"))
    )
    (net (code "41") (name "PH") (class "Default")
      (node (ref "C11") (pin "2") (pinfunction "2_2") (pintype "passive"))
      (node (ref "D2") (pin "3") (pinfunction "K_3") (pintype "passive"))
      (node (ref "U$10") (pin "1") (pinfunction "1_1") (pintype "passive"))
      (node (ref "U$2") (pin "8") (pinfunction "PH_8") (pintype "passive"))
    )
    (net (code "42") (name "PWM_C1") (class "Default")
      (node (ref "U$3") (pin "1") (pinfunction "P1.0_1") (pintype "power_in"))
    )
    (net (code "43") (name "PWM_C2") (class "Default")
      (node (ref "U$3") (pin "2") (pinfunction "P1.1_2") (pintype "power_in"))
    )
    (net (code "44") (name "PWM_C3") (class "Default")
      (node (ref "U$3") (pin "30") (pinfunction "P3.7_30") (pintype "power_in"))
    )
    (net (code "45") (name "PWM_C4") (class "Default")
      (node (ref "U$3") (pin "29") (pinfunction "P3.6_29") (pintype "power_in"))
    )
    (net (code "46") (name "PWM_C5") (class "Default")
      (node (ref "U$3") (pin "28") (pinfunction "P3.5_28") (pintype "power_in"))
    )
    (net (code "47") (name "PWM_C6") (class "Default")
      (node (ref "U$3") (pin "27") (pinfunction "P3.4_27") (pintype "power_in"))
    )
    (net (code "48") (name "PWM_C7") (class "Default")
      (node (ref "U$3") (pin "10") (pinfunction "P1.4_10") (pintype "power_in"))
    )
    (net (code "49") (name "PWM_C8") (class "Default")
      (node (ref "U$3") (pin "11") (pinfunction "P1.5_11") (pintype "power_in"))
    )
    (net (code "50") (name "PWM_C9") (class "Default")
      (node (ref "U$3") (pin "35") (pinfunction "P4.6_35") (pintype "power_in"))
    )
    (net (code "51") (name "PWM_C10") (class "Default")
      (node (ref "U$3") (pin "38") (pinfunction "P2.7_38") (pintype "power_in"))
    )
    (net (code "52") (name "PWM_C11") (class "Default")
      (node (ref "U$3") (pin "39") (pinfunction "P2.3_39") (pintype "power_in"))
    )
    (net (code "53") (name "PWM_C12") (class "Default")
      (node (ref "U$3") (pin "40") (pinfunction "P2.4_40") (pintype "power_in"))
    )
    (net (code "54") (name "PWM_IN_1") (class "Default")
      (node (ref "IN1") (pin "1") (pinfunction "1_1") (pintype "passive"))
    )
    (net (code "55") (name "PWM_IN_2") (class "Default")
      (node (ref "IN2") (pin "1") (pinfunction "1_1") (pintype "passive"))
    )
    (net (code "56") (name "PWM_IN_3") (class "Default")
      (node (ref "IN3") (pin "1") (pinfunction "1_1") (pintype "passive"))
    )
    (net (code "57") (name "PWM_IN_4") (class "Default")
      (node (ref "IN4") (pin "1") (pinfunction "1_1") (pintype "passive"))
    )
    (net (code "58") (name "PWM_IN_5") (class "Default")
      (node (ref "IN5") (pin "1") (pinfunction "1_1") (pintype "passive"))
    )
    (net (code "59") (name "PWM_IN_6") (class "Default")
      (node (ref "IN6") (pin "1") (pinfunction "1_1") (pintype "passive"))
    )
    (net (code "60") (name "PWM_IN_7") (class "Default")
      (node (ref "IN7") (pin "1") (pinfunction "1_1") (pintype "passive"))
    )
    (net (code "61") (name "PWM_IN_8") (class "Default")
      (node (ref "IN8") (pin "1") (pinfunction "1_1") (pintype "passive"))
    )
    (net (code "62") (name "PWM_OUT_1") (class "Default")
      (node (ref "O1") (pin "1") (pinfunction "1_1") (pintype "passive"))
    )
    (net (code "63") (name "PWM_OUT_2") (class "Default")
      (node (ref "O2") (pin "1") (pinfunction "1_1") (pintype "passive"))
    )
    (net (code "64") (name "PWM_OUT_3") (class "Default")
      (node (ref "O3") (pin "1") (pinfunction "1_1") (pintype "passive"))
    )
    (net (code "65") (name "PWM_OUT_4") (class "Default")
      (node (ref "O4") (pin "1") (pinfunction "1_1") (pintype "passive"))
    )
    (net (code "66") (name "RESET") (class "Default")
      (node (ref "C16") (pin "1") (pinfunction "1_1") (pintype "passive"))
      (node (ref "C34") (pin "1") (pinfunction "1_1") (pintype "passive"))
      (node (ref "R7") (pin "1") (pinfunction "1_1") (pintype "passive"))
      (node (ref "R8") (pin "2") (pinfunction "2_2") (pintype "passive"))
      (node (ref "RESET") (pin "B") (pinfunction "S_B") (pintype "passive"))
      (node (ref "RESET") (pin "B'") (pinfunction "S1_B'") (pintype "passive"))
      (node (ref "U$3") (pin "23") (pinfunction "RST_23") (pintype "power_in"))
    )
    (net (code "67") (name "SCL") (class "Default")
      (node (ref "U$1") (pin "P9.19") (pinfunction "I2C2_SCL_P9.19") (pintype "bidirectional"))
      (node (ref "U$4") (pin "1") (pinfunction "A_1_1") (pintype "bidirectional"))
    )
    (net (code "68") (name "SDA") (class "Default")
      (node (ref "U$1") (pin "P9.20") (pinfunction "I2C2_SDA_P9.20") (pintype "bidirectional"))
      (node (ref "U$4") (pin "4") (pinfunction "A_2_4") (pintype "bidirectional"))
    )
    (net (code "69") (name "SIMO") (class "Default")
      (node (ref "U$1") (pin "P9.30") (pinfunction "GPIO_122_P9.30") (pintype "bidirectional"))
      (node (ref "U$4") (pin "6") (pinfunction "B_2_6") (pintype "bidirectional"))
    )
    (net (code "70") (name "SIMO{slash}SDA") (class "Default")
      (node (ref "R11") (pin "1") (pinfunction "1_1") (pintype "passive"))
      (node (ref "U$3") (pin "31") (pinfunction "P1.6_31") (pintype "power_in"))
      (node (ref "U$4") (pin "5") (pinfunction "C_2_5") (pintype "bidirectional"))
    )
    (net (code "71") (name "SOMI") (class "Default")
      (node (ref "U$1") (pin "P9.29") (pinfunction "GPIO_121_P9.29") (pintype "bidirectional"))
      (node (ref "U$4") (pin "3") (pinfunction "B_1_3") (pintype "bidirectional"))
    )
    (net (code "72") (name "SOMI{slash}SCL") (class "Default")
      (node (ref "R10") (pin "1") (pinfunction "1_1") (pintype "passive"))
      (node (ref "U$3") (pin "32") (pinfunction "P1.7_32") (pintype "power_in"))
      (node (ref "U$4") (pin "2") (pinfunction "C_1_2") (pintype "bidirectional"))
    )
    (net (code "73") (name "SPI_CLK") (class "Default")
      (node (ref "U$1") (pin "P9.31") (pinfunction "GPIO_120_P9.31") (pintype "bidirectional"))
      (node (ref "U$3") (pin "26") (pinfunction "P2.2_26") (pintype "power_in"))
    )
    (net (code "74") (name "SPI_SL") (class "Default")
      (node (ref "SPDT") (pin "2") (pinfunction "C1_2") (pintype "bidirectional"))
      (node (ref "U$3") (pin "9") (pinfunction "P1.3_9") (pintype "power_in"))
    )
    (net (code "75") (name "SPI_SL0") (class "Default")
      (node (ref "SPDT") (pin "1") (pinfunction "A1_1") (pintype "bidirectional"))
      (node (ref "U$1") (pin "P9.28") (pinfunction "GPIO_123_P9.28") (pintype "bidirectional"))
    )
    (net (code "76") (name "SPI_SL1") (class "Default")
      (node (ref "SPDT") (pin "3") (pinfunction "B1_3") (pintype "bidirectional"))
      (node (ref "U$1") (pin "P9.42") (pinfunction "GPIO_7_P9.42") (pintype "bidirectional"))
    )
    (net (code "77") (name "TCK") (class "Default")
      (node (ref "U$12") (pin "8") (pinfunction "8_8") (pintype "passive"))
      (node (ref "U$3") (pin "15") (pinfunction "PJ.3_15") (pintype "power_in"))
    )
    (net (code "78") (name "TDI") (class "Default")
      (node (ref "U$12") (pin "4") (pinfunction "4_4") (pintype "passive"))
      (node (ref "U$3") (pin "13") (pinfunction "PJ.1_13") (pintype "power_in"))
    )
    (net (code "79") (name "TDO") (class "Default")
      (node (ref "U$12") (pin "2") (pinfunction "2_2") (pintype "passive"))
      (node (ref "U$3") (pin "12") (pinfunction "PJ.0_12") (pintype "power_in"))
    )
    (net (code "80") (name "TEST") (class "Default")
      (node (ref "U$12") (pin "7") (pinfunction "7_7") (pintype "passive"))
      (node (ref "U$3") (pin "22") (pinfunction "TEST_22") (pintype "power_in"))
    )
    (net (code "81") (name "TMS") (class "Default")
      (node (ref "U$12") (pin "6") (pinfunction "6_6") (pintype "passive"))
      (node (ref "U$3") (pin "14") (pinfunction "PJ.2_14") (pintype "power_in"))
    )
    (net (code "82") (name "TRIG_1") (class "Default")
      (node (ref "J1") (pin "2") (pinfunction "2_2") (pintype "passive"))
      (node (ref "U$3") (pin "21") (pinfunction "P2.6_21") (pintype "power_in"))
    )
    (net (code "83") (name "TRIG_2") (class "Default")
      (node (ref "J1") (pin "6") (pinfunction "6_6") (pintype "passive"))
      (node (ref "U$3") (pin "33") (pinfunction "P4.4_33") (pintype "power_in"))
    )
    (net (code "84") (name "TRIG_3") (class "Default")
      (node (ref "J1") (pin "10") (pinfunction "10_10") (pintype "passive"))
      (node (ref "U$3") (pin "34") (pinfunction "P4.5_34") (pintype "power_in"))
    )
    (net (code "85") (name "TRIG_4") (class "Default")
      (node (ref "J1") (pin "14") (pinfunction "14_14") (pintype "passive"))
      (node (ref "U$3") (pin "25") (pinfunction "P2.1_25") (pintype "power_in"))
    )
    (net (code "86") (name "TRIG_5") (class "Default")
      (node (ref "J1") (pin "18") (pinfunction "18_18") (pintype "passive"))
      (node (ref "U$3") (pin "24") (pinfunction "P2.0_24") (pintype "power_in"))
    )
    (net (code "87") (name "TRIG_6") (class "Default")
      (node (ref "J2") (pin "2") (pinfunction "2_2") (pintype "passive"))
      (node (ref "U$3") (pin "3") (pinfunction "P1.2_3") (pintype "power_in"))
    )
    (net (code "88") (name "TRIG_7") (class "Default")
      (node (ref "J2") (pin "6") (pinfunction "6_6") (pintype "passive"))
      (node (ref "U$3") (pin "46") (pinfunction "PJ.5_46") (pintype "power_in"))
    )
    (net (code "89") (name "TRIG_8") (class "Default")
      (node (ref "J2") (pin "10") (pinfunction "10_10") (pintype "passive"))
      (node (ref "U$3") (pin "45") (pinfunction "PJ.4_45") (pintype "power_in"))
    )
    (net (code "90") (name "TRIG_9") (class "Default")
      (node (ref "J2") (pin "14") (pinfunction "14_14") (pintype "passive"))
      (node (ref "U$3") (pin "43") (pinfunction "PJ.7_43") (pintype "power_in"))
    )
    (net (code "91") (name "TRIG_10") (class "Default")
      (node (ref "J2") (pin "18") (pinfunction "18_18") (pintype "passive"))
      (node (ref "U$3") (pin "42") (pinfunction "PJ.6_42") (pintype "power_in"))
    )
    (net (code "92") (name "T_PAD") (class "Default")
      (node (ref "U$3") (pin "49") (pinfunction "T_PAD_49") (pintype "power_in"))
    )
    (net (code "93") (name "VCC") (class "Default")
      (node (ref "C10") (pin "2") (pinfunction "2_2") (pintype "passive"))
      (node (ref "C19") (pin "2") (pinfunction "2_2") (pintype "passive"))
      (node (ref "C20") (pin "2") (pinfunction "2_2") (pintype "passive"))
      (node (ref "C21") (pin "2") (pinfunction "2_2") (pintype "passive"))
      (node (ref "D1") (pin "C") (pinfunction "C_C") (pintype "passive"))
      (node (ref "R1") (pin "2") (pinfunction "2_2") (pintype "passive"))
      (node (ref "U$2") (pin "7") (pinfunction "VIN_7") (pintype "passive"))
    )
    (net (code "94") (name "unconnected-(U$1A-GPIO_8-PadP8.35)") (class "Default")
      (node (ref "U$1") (pin "P8.35") (pinfunction "GPIO_8_P8.35") (pintype "bidirectional"))
    )
    (net (code "95") (name "unconnected-(U$1A-GPIO_9-PadP8.33)") (class "Default")
      (node (ref "U$1") (pin "P8.33") (pinfunction "GPIO_9_P8.33") (pintype "bidirectional"))
    )
    (net (code "96") (name "unconnected-(U$1A-GPIO_10-PadP8.31)") (class "Default")
      (node (ref "U$1") (pin "P8.31") (pinfunction "GPIO_10_P8.31") (pintype "bidirectional"))
    )
    (net (code "97") (name "unconnected-(U$1A-GPIO_11-PadP8.32)") (class "Default")
      (node (ref "U$1") (pin "P8.32") (pinfunction "GPIO_11_P8.32") (pintype "bidirectional"))
    )
    (net (code "98") (name "unconnected-(U$1A-GPIO_22-PadP8.19)") (class "Default")
      (node (ref "U$1") (pin "P8.19") (pinfunction "GPIO_22_P8.19") (pintype "bidirectional"))
    )
    (net (code "99") (name "unconnected-(U$1A-GPIO_23-PadP8.13)") (class "Default")
      (node (ref "U$1") (pin "P8.13") (pinfunction "GPIO_23_P8.13") (pintype "bidirectional"))
    )
    (net (code "100") (name "unconnected-(U$1A-GPIO_26-PadP8.14)") (class "Default")
      (node (ref "U$1") (pin "P8.14") (pinfunction "GPIO_26_P8.14") (pintype "bidirectional"))
    )
    (net (code "101") (name "unconnected-(U$1A-GPIO_27-PadP8.17)") (class "Default")
      (node (ref "U$1") (pin "P8.17") (pinfunction "GPIO_27_P8.17") (pintype "bidirectional"))
    )
    (net (code "102") (name "unconnected-(U$1A-GPIO_32-PadP8.25)") (class "Default")
      (node (ref "U$1") (pin "P8.25") (pinfunction "GPIO_32_P8.25") (pintype "bidirectional"))
    )
    (net (code "103") (name "unconnected-(U$1A-GPIO_33-PadP8.24)") (class "Default")
      (node (ref "U$1") (pin "P8.24") (pinfunction "GPIO_33_P8.24") (pintype "bidirectional"))
    )
    (net (code "104") (name "unconnected-(U$1A-GPIO_34-PadP8.5)") (class "Default")
      (node (ref "U$1") (pin "P8.5") (pinfunction "GPIO_34_P8.5") (pintype "bidirectional"))
    )
    (net (code "105") (name "unconnected-(U$1A-GPIO_35-PadP8.6)") (class "Default")
      (node (ref "U$1") (pin "P8.6") (pinfunction "GPIO_35_P8.6") (pintype "bidirectional"))
    )
    (net (code "106") (name "unconnected-(U$1A-GPIO_36-PadP8.23)") (class "Default")
      (node (ref "U$1") (pin "P8.23") (pinfunction "GPIO_36_P8.23") (pintype "bidirectional"))
    )
    (net (code "107") (name "unconnected-(U$1A-GPIO_37-PadP8.22)") (class "Default")
      (node (ref "U$1") (pin "P8.22") (pinfunction "GPIO_37_P8.22") (pintype "bidirectional"))
    )
    (net (code "108") (name "unconnected-(U$1A-GPIO_38-PadP8.3)") (class "Default")
      (node (ref "U$1") (pin "P8.3") (pinfunction "GPIO_38_P8.3") (pintype "bidirectional"))
    )
    (net (code "109") (name "unconnected-(U$1A-GPIO_39-PadP8.4)") (class "Default")
      (node (ref "U$1") (pin "P8.4") (pinfunction "GPIO_39_P8.4") (pintype "bidirectional"))
    )
    (net (code "110") (name "unconnected-(U$1A-GPIO_44-PadP8.12)") (class "Default")
      (node (ref "U$1") (pin "P8.12") (pinfunction "GPIO_44_P8.12") (pintype "bidirectional"))
    )
    (net (code "111") (name "unconnected-(U$1A-GPIO_45-PadP8.11)") (class "Default")
      (node (ref "U$1") (pin "P8.11") (pinfunction "GPIO_45_P8.11") (pintype "bidirectional"))
    )
    (net (code "112") (name "unconnected-(U$1A-GPIO_46-PadP8.16)") (class "Default")
      (node (ref "U$1") (pin "P8.16") (pinfunction "GPIO_46_P8.16") (pintype "bidirectional"))
    )
    (net (code "113") (name "unconnected-(U$1A-GPIO_47-PadP8.15)") (class "Default")
      (node (ref "U$1") (pin "P8.15") (pinfunction "GPIO_47_P8.15") (pintype "bidirectional"))
    )
    (net (code "114") (name "unconnected-(U$1A-GPIO_61-PadP8.26)") (class "Default")
      (node (ref "U$1") (pin "P8.26") (pinfunction "GPIO_61_P8.26") (pintype "bidirectional"))
    )
    (net (code "115") (name "unconnected-(U$1A-GPIO_62-PadP8.21)") (class "Default")
      (node (ref "U$1") (pin "P8.21") (pinfunction "GPIO_62_P8.21") (pintype "bidirectional"))
    )
    (net (code "116") (name "unconnected-(U$1A-GPIO_63-PadP8.20)") (class "Default")
      (node (ref "U$1") (pin "P8.20") (pinfunction "GPIO_63_P8.20") (pintype "bidirectional"))
    )
    (net (code "117") (name "unconnected-(U$1A-GPIO_65-PadP8.18)") (class "Default")
      (node (ref "U$1") (pin "P8.18") (pinfunction "GPIO_65_P8.18") (pintype "bidirectional"))
    )
    (net (code "118") (name "unconnected-(U$1A-GPIO_66-PadP8.7)") (class "Default")
      (node (ref "U$1") (pin "P8.7") (pinfunction "GPIO_66_P8.7") (pintype "bidirectional"))
    )
    (net (code "119") (name "unconnected-(U$1A-GPIO_67-PadP8.8)") (class "Default")
      (node (ref "U$1") (pin "P8.8") (pinfunction "GPIO_67_P8.8") (pintype "bidirectional"))
    )
    (net (code "120") (name "unconnected-(U$1A-GPIO_68-PadP8.10)") (class "Default")
      (node (ref "U$1") (pin "P8.10") (pinfunction "GPIO_68_P8.10") (pintype "bidirectional"))
    )
    (net (code "121") (name "unconnected-(U$1A-GPIO_69-PadP8.9)") (class "Default")
      (node (ref "U$1") (pin "P8.9") (pinfunction "GPIO_69_P8.9") (pintype "bidirectional"))
    )
    (net (code "122") (name "unconnected-(U$1A-GPIO_70-PadP8.45)") (class "Default")
      (node (ref "U$1") (pin "P8.45") (pinfunction "GPIO_70_P8.45") (pintype "bidirectional"))
    )
    (net (code "123") (name "unconnected-(U$1A-GPIO_71-PadP8.46)") (class "Default")
      (node (ref "U$1") (pin "P8.46") (pinfunction "GPIO_71_P8.46") (pintype "bidirectional"))
    )
    (net (code "124") (name "unconnected-(U$1A-GPIO_72-PadP8.43)") (class "Default")
      (node (ref "U$1") (pin "P8.43") (pinfunction "GPIO_72_P8.43") (pintype "bidirectional"))
    )
    (net (code "125") (name "unconnected-(U$1A-GPIO_73-PadP8.44)") (class "Default")
      (node (ref "U$1") (pin "P8.44") (pinfunction "GPIO_73_P8.44") (pintype "bidirectional"))
    )
    (net (code "126") (name "unconnected-(U$1A-GPIO_74-PadP8.41)") (class "Default")
      (node (ref "U$1") (pin "P8.41") (pinfunction "GPIO_74_P8.41") (pintype "bidirectional"))
    )
    (net (code "127") (name "unconnected-(U$1A-GPIO_75-PadP8.42)") (class "Default")
      (node (ref "U$1") (pin "P8.42") (pinfunction "GPIO_75_P8.42") (pintype "bidirectional"))
    )
    (net (code "128") (name "unconnected-(U$1A-GPIO_76-PadP8.39)") (class "Default")
      (node (ref "U$1") (pin "P8.39") (pinfunction "GPIO_76_P8.39") (pintype "bidirectional"))
    )
    (net (code "129") (name "unconnected-(U$1A-GPIO_77-PadP8.40)") (class "Default")
      (node (ref "U$1") (pin "P8.40") (pinfunction "GPIO_77_P8.40") (pintype "bidirectional"))
    )
    (net (code "130") (name "unconnected-(U$1A-GPIO_78-PadP8.37)") (class "Default")
      (node (ref "U$1") (pin "P8.37") (pinfunction "GPIO_78_P8.37") (pintype "bidirectional"))
    )
    (net (code "131") (name "unconnected-(U$1A-GPIO_79-PadP8.38)") (class "Default")
      (node (ref "U$1") (pin "P8.38") (pinfunction "GPIO_79_P8.38") (pintype "bidirectional"))
    )
    (net (code "132") (name "unconnected-(U$1A-GPIO_80-PadP8.36)") (class "Default")
      (node (ref "U$1") (pin "P8.36") (pinfunction "GPIO_80_P8.36") (pintype "bidirectional"))
    )
    (net (code "133") (name "unconnected-(U$1A-GPIO_81-PadP8.34)") (class "Default")
      (node (ref "U$1") (pin "P8.34") (pinfunction "GPIO_81_P8.34") (pintype "bidirectional"))
    )
    (net (code "134") (name "unconnected-(U$1A-GPIO_86-PadP8.27)") (class "Default")
      (node (ref "U$1") (pin "P8.27") (pinfunction "GPIO_86_P8.27") (pintype "bidirectional"))
    )
    (net (code "135") (name "unconnected-(U$1A-GPIO_87-PadP8.29)") (class "Default")
      (node (ref "U$1") (pin "P8.29") (pinfunction "GPIO_87_P8.29") (pintype "bidirectional"))
    )
    (net (code "136") (name "unconnected-(U$1A-GPIO_88-PadP8.28)") (class "Default")
      (node (ref "U$1") (pin "P8.28") (pinfunction "GPIO_88_P8.28") (pintype "bidirectional"))
    )
    (net (code "137") (name "unconnected-(U$1A-GPIO_89-PadP8.30)") (class "Default")
      (node (ref "U$1") (pin "P8.30") (pinfunction "GPIO_89_P8.30") (pintype "bidirectional"))
    )
    (net (code "138") (name "unconnected-(U$1B-AIN0-PadP9.39)") (class "Default")
      (node (ref "U$1") (pin "P9.39") (pinfunction "AIN0_P9.39") (pintype "bidirectional"))
    )
    (net (code "139") (name "unconnected-(U$1B-AIN1-PadP9.40)") (class "Default")
      (node (ref "U$1") (pin "P9.40") (pinfunction "AIN1_P9.40") (pintype "bidirectional"))
    )
    (net (code "140") (name "unconnected-(U$1B-AIN2-PadP9.37)") (class "Default")
      (node (ref "U$1") (pin "P9.37") (pinfunction "AIN2_P9.37") (pintype "bidirectional"))
    )
    (net (code "141") (name "unconnected-(U$1B-AIN3-PadP9.38)") (class "Default")
      (node (ref "U$1") (pin "P9.38") (pinfunction "AIN3_P9.38") (pintype "bidirectional"))
    )
    (net (code "142") (name "unconnected-(U$1B-AIN4-PadP9.33)") (class "Default")
      (node (ref "U$1") (pin "P9.33") (pinfunction "AIN4_P9.33") (pintype "bidirectional"))
    )
    (net (code "143") (name "unconnected-(U$1B-AIN5-PadP9.36)") (class "Default")
      (node (ref "U$1") (pin "P9.36") (pinfunction "AIN5_P9.36") (pintype "bidirectional"))
    )
    (net (code "144") (name "unconnected-(U$1B-AIN6-PadP9.35)") (class "Default")
      (node (ref "U$1") (pin "P9.35") (pinfunction "AIN6_P9.35") (pintype "bidirectional"))
    )
    (net (code "145") (name "unconnected-(U$1B-DGND-PadP9.43)") (class "Default")
      (node (ref "U$1") (pin "P9.43") (pinfunction "DGND_P9.43") (pintype "bidirectional"))
    )
    (net (code "146") (name "unconnected-(U$1B-DGND-PadP9.44)") (class "Default")
      (node (ref "U$1") (pin "P9.44") (pinfunction "DGND_P9.44") (pintype "bidirectional"))
    )
    (net (code "147") (name "unconnected-(U$1B-DGND-PadP9.45)") (class "Default")
      (node (ref "U$1") (pin "P9.45") (pinfunction "DGND_P9.45") (pintype "bidirectional"))
    )
    (net (code "148") (name "unconnected-(U$1B-DGND-PadP9.46)") (class "Default")
      (node (ref "U$1") (pin "P9.46") (pinfunction "DGND_P9.46") (pintype "bidirectional"))
    )
    (net (code "149") (name "unconnected-(U$1B-GNDA_ADC-PadP9.34)") (class "Default")
      (node (ref "U$1") (pin "P9.34") (pinfunction "GNDA_ADC_P9.34") (pintype "bidirectional"))
    )
    (net (code "150") (name "unconnected-(U$1B-GPIO_3-PadP9.21)") (class "Default")
      (node (ref "U$1") (pin "P9.21") (pinfunction "GPIO_3_P9.21") (pintype "bidirectional"))
    )
    (net (code "151") (name "unconnected-(U$1B-GPIO_4-PadP9.17)") (class "Default")
      (node (ref "U$1") (pin "P9.17") (pinfunction "GPIO_4_P9.17") (pintype "bidirectional"))
    )
    (net (code "152") (name "unconnected-(U$1B-GPIO_5-PadP9.18)") (class "Default")
      (node (ref "U$1") (pin "P9.18") (pinfunction "GPIO_5_P9.18") (pintype "bidirectional"))
    )
    (net (code "153") (name "unconnected-(U$1B-GPIO_20-PadP9.41)") (class "Default")
      (node (ref "U$1") (pin "P9.41") (pinfunction "GPIO_20_P9.41") (pintype "bidirectional"))
    )
    (net (code "154") (name "unconnected-(U$1B-GPIO_30-PadP9.11)") (class "Default")
      (node (ref "U$1") (pin "P9.11") (pinfunction "GPIO_30_P9.11") (pintype "bidirectional"))
    )
    (net (code "155") (name "unconnected-(U$1B-GPIO_31-PadP9.13)") (class "Default")
      (node (ref "U$1") (pin "P9.13") (pinfunction "GPIO_31_P9.13") (pintype "bidirectional"))
    )
    (net (code "156") (name "unconnected-(U$1B-GPIO_40-PadP9.14)") (class "Default")
      (node (ref "U$1") (pin "P9.14") (pinfunction "GPIO_40_P9.14") (pintype "bidirectional"))
    )
    (net (code "157") (name "unconnected-(U$1B-GPIO_48-PadP9.15)") (class "Default")
      (node (ref "U$1") (pin "P9.15") (pinfunction "GPIO_48_P9.15") (pintype "bidirectional"))
    )
    (net (code "158") (name "unconnected-(U$1B-GPIO_51-PadP9.16)") (class "Default")
      (node (ref "U$1") (pin "P9.16") (pinfunction "GPIO_51_P9.16") (pintype "bidirectional"))
    )
    (net (code "159") (name "unconnected-(U$1B-GPIO_60-PadP9.12)") (class "Default")
      (node (ref "U$1") (pin "P9.12") (pinfunction "GPIO_60_P9.12") (pintype "bidirectional"))
    )
    (net (code "160") (name "unconnected-(U$1B-GPIO_117-PadP9.25)") (class "Default")
      (node (ref "U$1") (pin "P9.25") (pinfunction "GPIO_117_P9.25") (pintype "bidirectional"))
    )
    (net (code "161") (name "unconnected-(U$1B-GPIO_125-PadP9.27)") (class "Default")
      (node (ref "U$1") (pin "P9.27") (pinfunction "GPIO_125_P9.27") (pintype "bidirectional"))
    )
    (net (code "162") (name "unconnected-(U$1B-PWR_BUT-PadP9.9)") (class "Default")
      (node (ref "U$1") (pin "P9.9") (pinfunction "PWR_BUT_P9.9") (pintype "bidirectional"))
    )
    (net (code "163") (name "unconnected-(U$1B-SYS_5V-PadP9.7)") (class "Default")
      (node (ref "U$1") (pin "P9.7") (pinfunction "SYS_5V_P9.7") (pintype "bidirectional"))
    )
    (net (code "164") (name "unconnected-(U$1B-SYS_5V-PadP9.8)") (class "Default")
      (node (ref "U$1") (pin "P9.8") (pinfunction "SYS_5V_P9.8") (pintype "bidirectional"))
    )
    (net (code "165") (name "unconnected-(U$1B-SYS_RESET~{N}-PadP9.10)") (class "Default")
      (node (ref "U$1") (pin "P9.10") (pinfunction "SYS_RESET~{N}_P9.10") (pintype "bidirectional"))
    )
    (net (code "166") (name "unconnected-(U$1B-VDD_3V3-PadP9.3)") (class "Default")
      (node (ref "U$1") (pin "P9.3") (pinfunction "VDD_3V3_P9.3") (pintype "bidirectional"))
    )
    (net (code "167") (name "unconnected-(U$1B-VDD_3V3-PadP9.4)") (class "Default")
      (node (ref "U$1") (pin "P9.4") (pinfunction "VDD_3V3_P9.4") (pintype "bidirectional"))
    )
    (net (code "168") (name "unconnected-(U$1B-VDD_ADC-PadP9.32)") (class "Default")
      (node (ref "U$1") (pin "P9.32") (pinfunction "VDD_ADC_P9.32") (pintype "bidirectional"))
    )
    (net (code "169") (name "unconnected-(U$6-A1-Pad1)") (class "Default")
      (node (ref "U$6") (pin "1") (pinfunction "A1_1") (pintype "bidirectional"))
    )
    (net (code "170") (name "unconnected-(U$6-A7-Pad8)") (class "Default")
      (node (ref "U$6") (pin "8") (pinfunction "A7_8") (pintype "bidirectional"))
    )
    (net (code "171") (name "unconnected-(U$6-A8-Pad9)") (class "Default")
      (node (ref "U$6") (pin "9") (pinfunction "A8_9") (pintype "bidirectional"))
    )
    (net (code "172") (name "unconnected-(U$6-B1-Pad20)") (class "Default")
      (node (ref "U$6") (pin "20") (pinfunction "B1_20") (pintype "bidirectional"))
    )
    (net (code "173") (name "unconnected-(U$6-B7-Pad13)") (class "Default")
      (node (ref "U$6") (pin "13") (pinfunction "B7_13") (pintype "bidirectional"))
    )
    (net (code "174") (name "unconnected-(U$6-B8-Pad12)") (class "Default")
      (node (ref "U$6") (pin "12") (pinfunction "B8_12") (pintype "bidirectional"))
    )
    (net (code "175") (name "unconnected-(U$8-A1-Pad1)") (class "Default")
      (node (ref "U$8") (pin "1") (pinfunction "A1_1") (pintype "bidirectional"))
    )
    (net (code "176") (name "unconnected-(U$8-A7-Pad8)") (class "Default")
      (node (ref "U$8") (pin "8") (pinfunction "A7_8") (pintype "bidirectional"))
    )
    (net (code "177") (name "unconnected-(U$8-A8-Pad9)") (class "Default")
      (node (ref "U$8") (pin "9") (pinfunction "A8_9") (pintype "bidirectional"))
    )
    (net (code "178") (name "unconnected-(U$8-B1-Pad20)") (class "Default")
      (node (ref "U$8") (pin "20") (pinfunction "B1_20") (pintype "bidirectional"))
    )
    (net (code "179") (name "unconnected-(U$8-B7-Pad13)") (class "Default")
      (node (ref "U$8") (pin "13") (pinfunction "B7_13") (pintype "bidirectional"))
    )
    (net (code "180") (name "unconnected-(U$8-B8-Pad12)") (class "Default")
      (node (ref "U$8") (pin "12") (pinfunction "B8_12") (pintype "bidirectional"))
    )
    (net (code "181") (name "unconnected-(U$12-Pad3)") (class "Default")
      (node (ref "U$12") (pin "3") (pinfunction "3_3") (pintype "passive"))
    )
    (net (code "182") (name "unconnected-(U$12-Pad5)") (class "Default")
      (node (ref "U$12") (pin "5") (pinfunction "5_5") (pintype "passive"))
    )
    (net (code "183") (name "unconnected-(U$12-Pad13)") (class "Default")
      (node (ref "U$12") (pin "13") (pinfunction "13_13") (pintype "passive"))
    )
    (net (code "184") (name "unconnected-(U$12-Pad14)") (class "Default")
      (node (ref "U$12") (pin "14") (pinfunction "14_14") (pintype "passive"))
    )
    (net (code "185") (name "unconnected-(U5-OUT-Pad2)") (class "Default")
      (node (ref "U5") (pin "2") (pinfunction "OUT_2") (pintype "output"))
    )
  )
)
